# zx80_SD_12_smd_build006_3_STM32.net
KiCad netlist of a schematic drawn in EAGLE
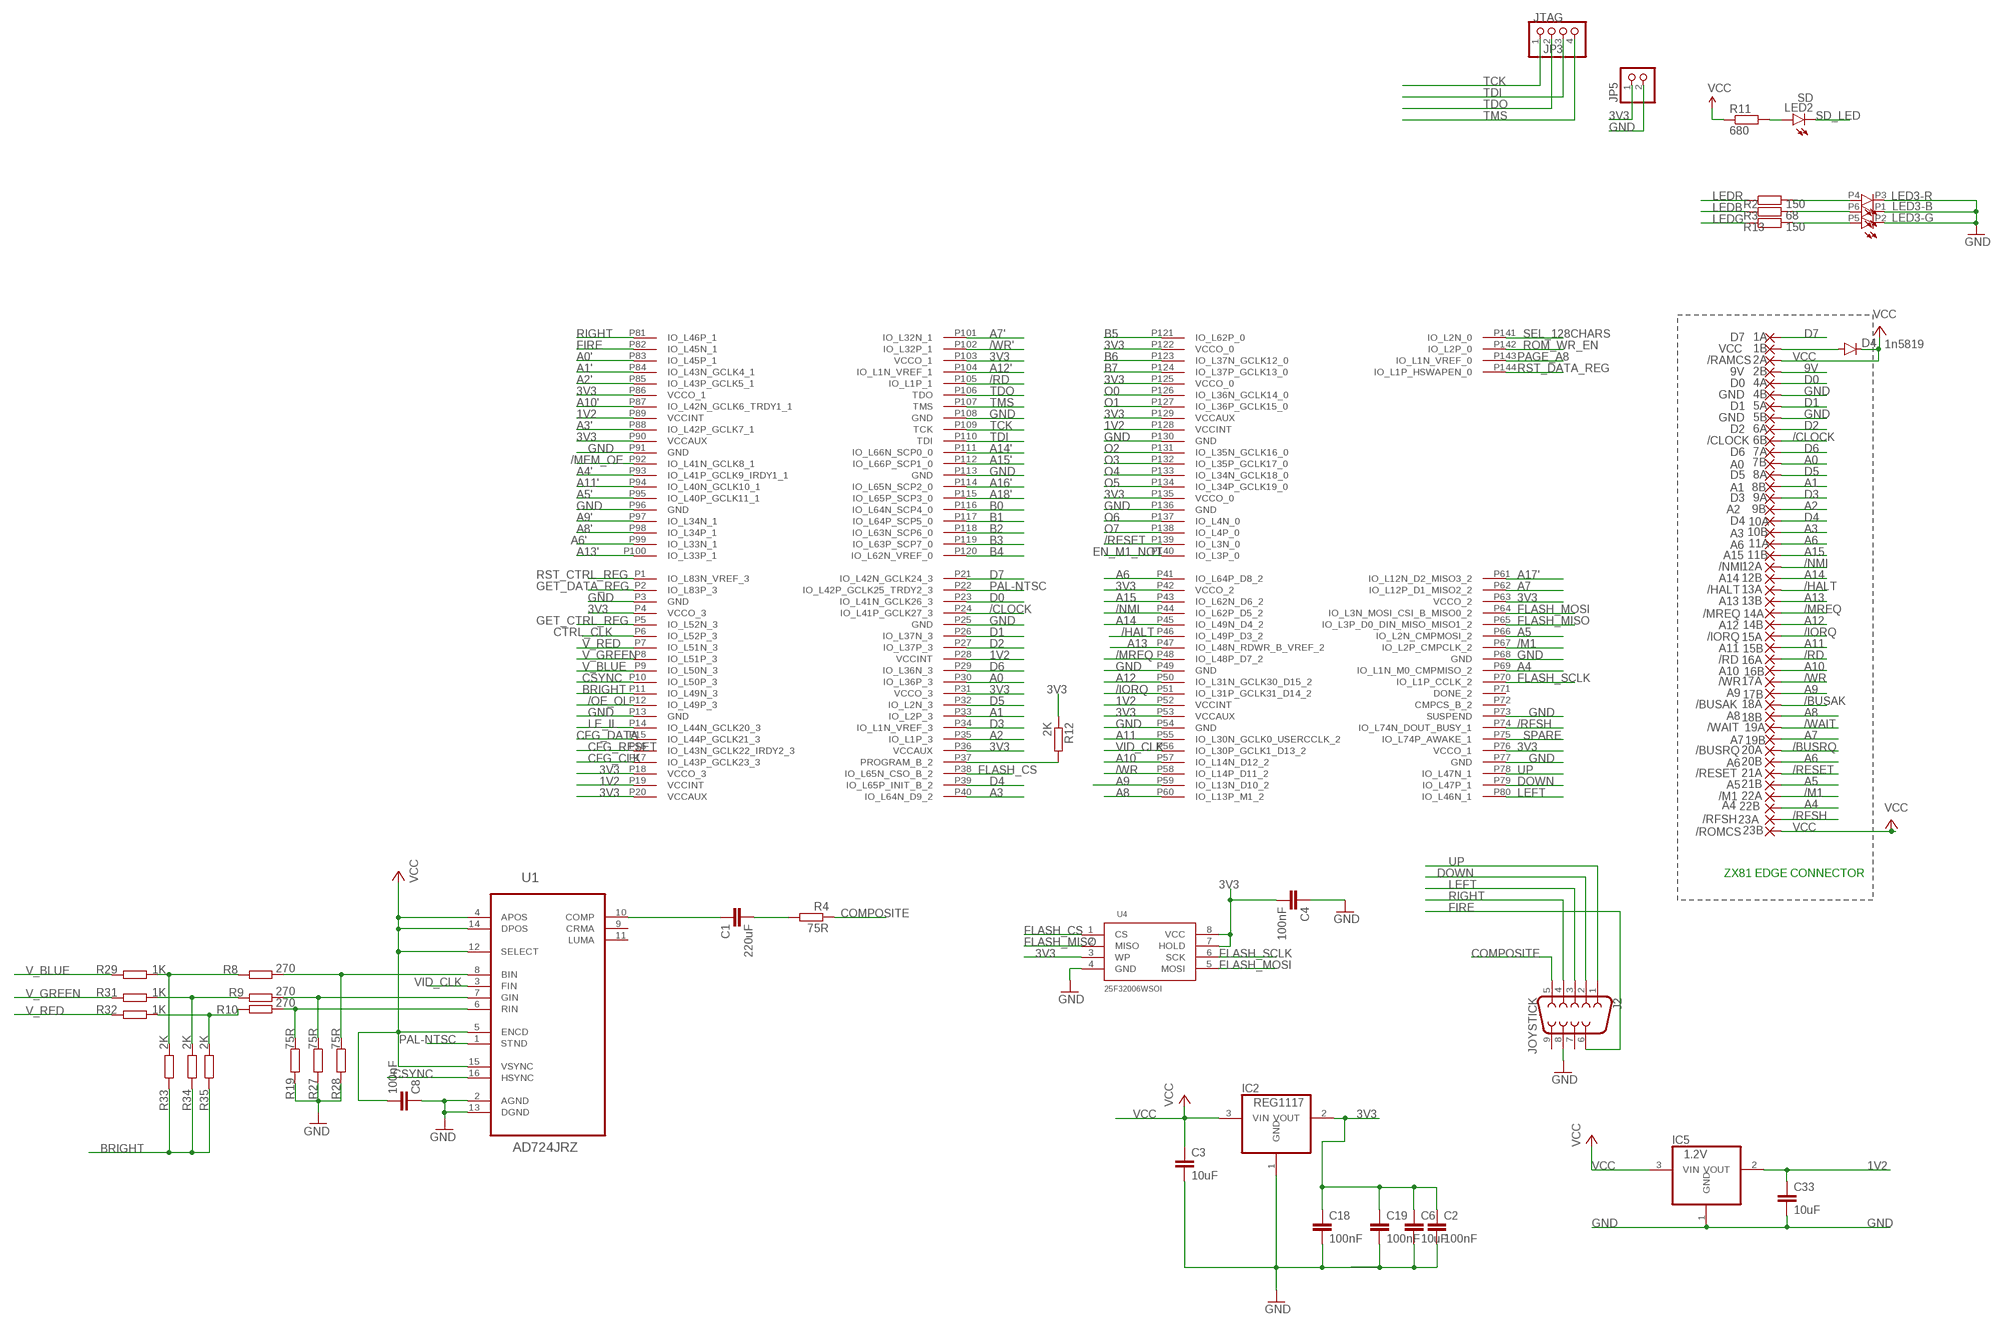
[diagram p0: schematic, sheet 1, part 1 of 2]
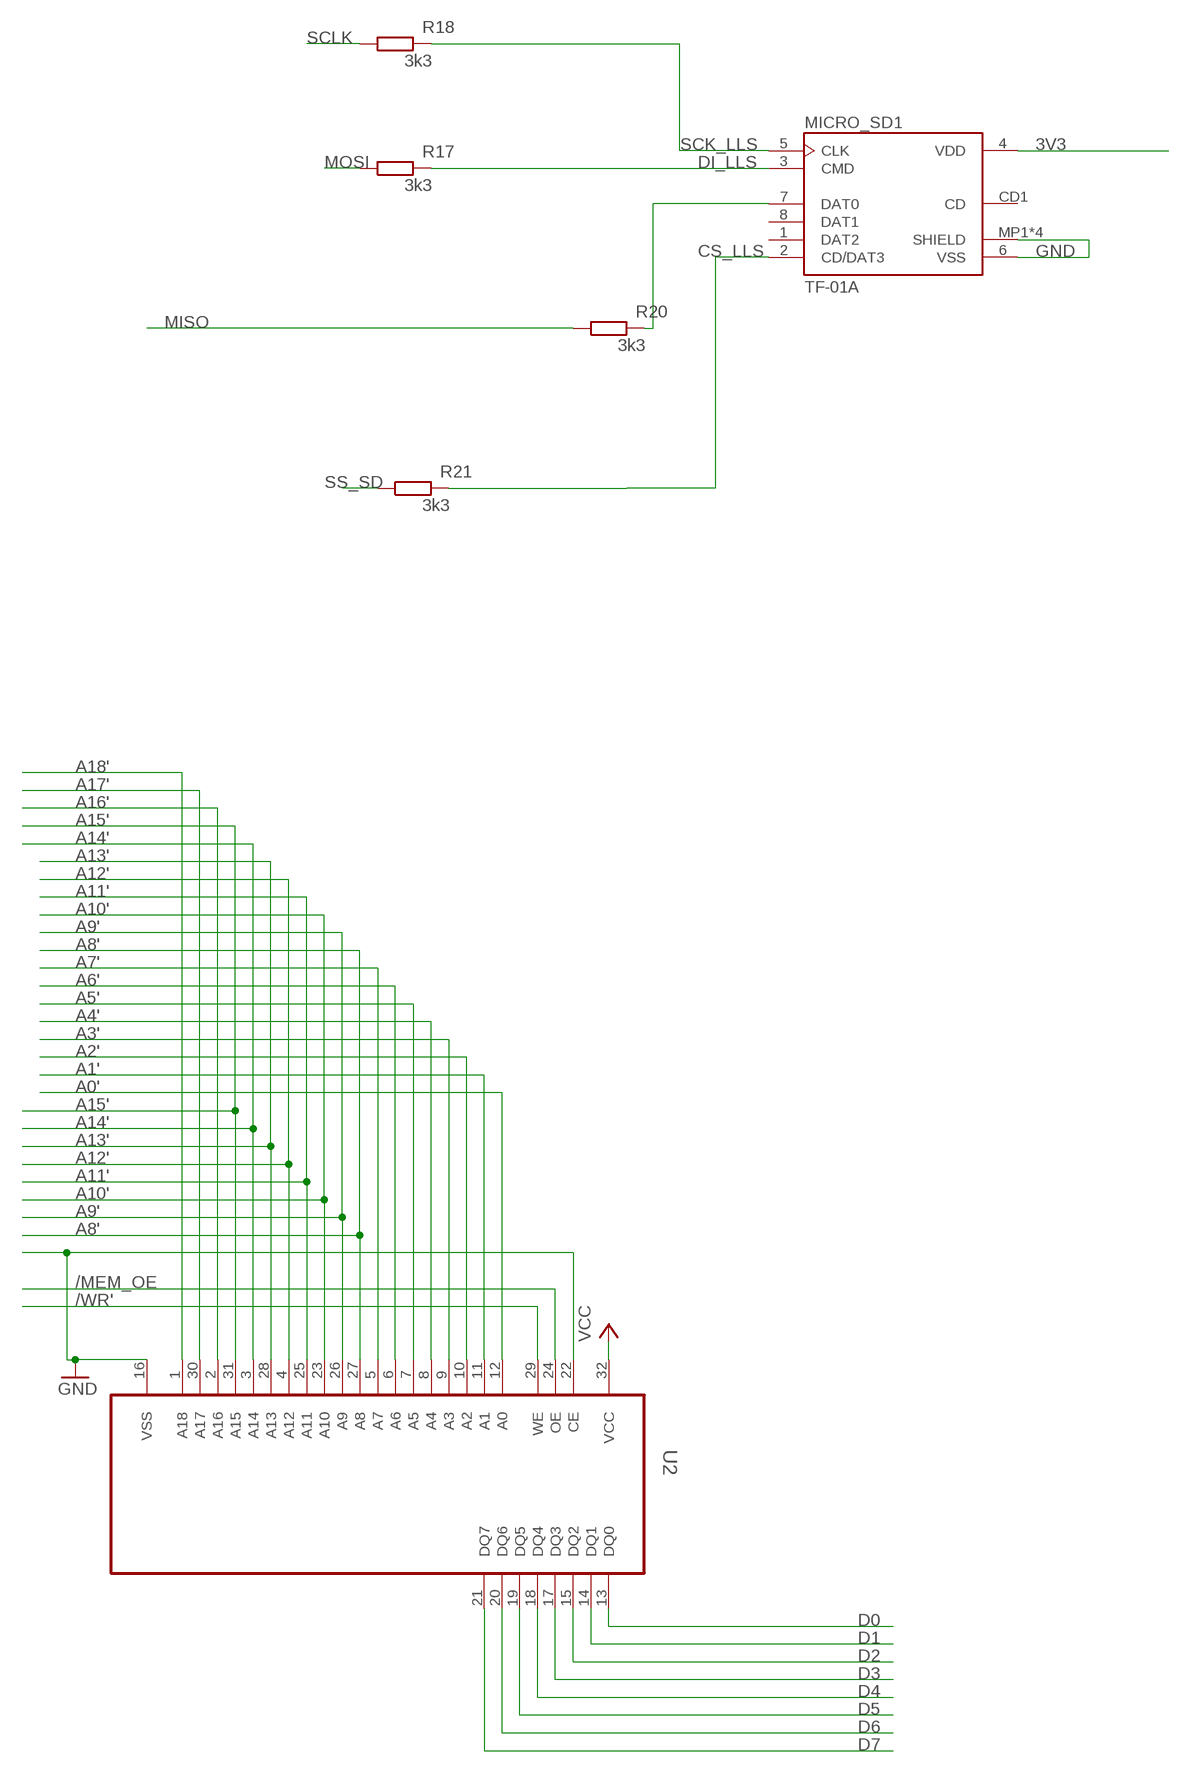
[diagram p1: schematic, sheet 1, part 2 of 2]
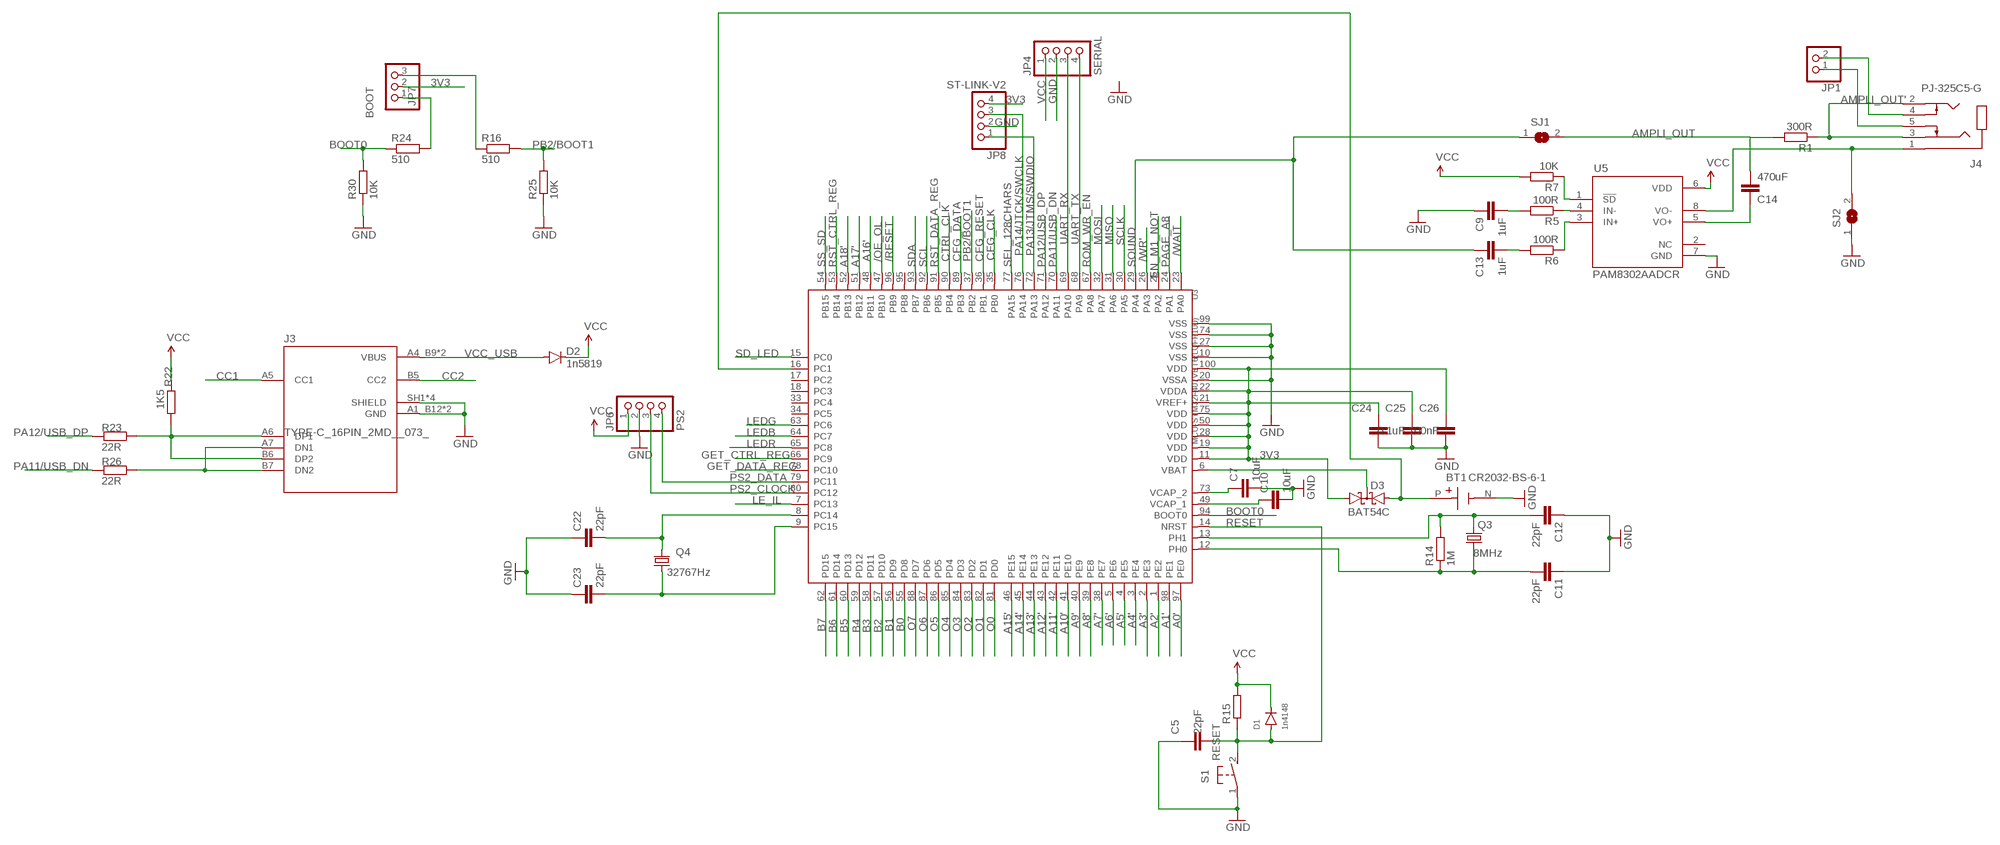
[diagram p2: schematic, sheet 2]

(export (version "E")
  (design (tool "Eeschema 10.0.6"))
  (components
    (comp (ref "BT1")
      (value "CR2032-BS-6-1")
      (footprint "eagle-import:BAT_CR2032-BS-6-1")
      (fields (field (name "MF") "Shenzhen Q&J Electronics Co. Ltd"))
      (libsource (lib "eagle-import") (part "CR2032-BS-6-1"))
    )
    (comp (ref "C5")
      (value "22pF")
      (footprint "eagle-import:C0603")
      (libsource (lib "eagle-import") (part "C-EUC0603"))
    )
    (comp (ref "C7")
      (value "10uF")
      (footprint "eagle-import:C1206")
      (libsource (lib "eagle-import") (part "C-EUC1206"))
    )
    (comp (ref "C9")
      (value "1uF")
      (footprint "eagle-import:C0603")
      (libsource (lib "eagle-import") (part "C-EUC0603"))
    )
    (comp (ref "C10")
      (value "10uF")
      (footprint "eagle-import:C1206")
      (libsource (lib "eagle-import") (part "C-EUC1206"))
    )
    (comp (ref "C11")
      (value "22pF")
      (footprint "eagle-import:C0603")
      (libsource (lib "eagle-import") (part "C-EUC0603"))
    )
    (comp (ref "C12")
      (value "22pF")
      (footprint "eagle-import:C0603")
      (libsource (lib "eagle-import") (part "C-EUC0603"))
    )
    (comp (ref "C13")
      (value "1uF")
      (footprint "eagle-import:C0603")
      (libsource (lib "eagle-import") (part "C-EUC0603"))
    )
    (comp (ref "C14")
      (value "470uF")
      (footprint "eagle-import:C0603")
      (libsource (lib "eagle-import") (part "C-EUC0603"))
    )
    (comp (ref "C22")
      (value "22pF")
      (footprint "eagle-import:C0603")
      (libsource (lib "eagle-import") (part "C-EUC0603"))
    )
    (comp (ref "C23")
      (value "22pF")
      (footprint "eagle-import:C0603")
      (libsource (lib "eagle-import") (part "C-EUC0603"))
    )
    (comp (ref "C24")
      (value "0.1uF")
      (footprint "eagle-import:C0603")
      (libsource (lib "eagle-import") (part "C-EUC0603"))
    )
    (comp (ref "C25")
      (value "0.1uF")
      (footprint "eagle-import:C0603")
      (libsource (lib "eagle-import") (part "C-EUC0603"))
    )
    (comp (ref "C26")
      (value "100nF")
      (footprint "eagle-import:C0603")
      (libsource (lib "eagle-import") (part "C-EUC0603"))
    )
    (comp (ref "D1")
      (value "1n4148")
      (footprint "eagle-import:SOD123")
      (libsource (lib "eagle-import") (part "DIODE-SOD123"))
    )
    (comp (ref "D2")
      (value "1n5819")
      (footprint "eagle-import:SOD323-W")
      (libsource (lib "eagle-import") (part "DIODE-SOD323-W"))
    )
    (comp (ref "D3")
      (value "BAT54C")
      (footprint "eagle-import:SOT23")
      (libsource (lib "eagle-import") (part "BAT54C"))
    )
    (comp (ref "J3")
      (value "TYPE-C_16PIN_2MD__073_")
      (footprint "eagle-import:SHOUHAN_TYPE-C_16PIN_2MD__073_")
      (fields (field (name "MF") "Shouhan") (field (name "MP") "TYPE-C 16PIN 2MD (073)"))
      (libsource (lib "eagle-import") (part "TYPE-C_16PIN_2MD__073_"))
    )
    (comp (ref "J4")
      (value "PJ-325C5-G")
      (footprint "eagle-import:XKB_PJ-325C5-G")
      (fields (field (name "MF") "XKB Connection"))
      (libsource (lib "eagle-import") (part "PJ-325C5-G"))
    )
    (comp (ref "JP1")
      (value "PINHD-1X2")
      (footprint "eagle-import:1X02")
      (libsource (lib "eagle-import") (part "PINHD-1X2"))
    )
    (comp (ref "JP4")
      (value "SERIAL")
      (footprint "eagle-import:1X04")
      (libsource (lib "eagle-import") (part "PINHD-1X4"))
    )
    (comp (ref "JP6")
      (value "PS2")
      (footprint "eagle-import:1X04")
      (libsource (lib "eagle-import") (part "PINHD-1X4"))
    )
    (comp (ref "JP7")
      (value "BOOT")
      (footprint "eagle-import:1X03")
      (libsource (lib "eagle-import") (part "PINHD-1X3"))
    )
    (comp (ref "JP8")
      (value "ST-LINK-V2")
      (footprint "eagle-import:1X04")
      (libsource (lib "eagle-import") (part "PINHD-1X4"))
    )
    (comp (ref "Q3")
      (value "8MHz")
      (footprint "eagle-import:3.2X2.5_KX-7")
      (libsource (lib "eagle-import") (part "KX-7"))
    )
    (comp (ref "Q4")
      (value "32767Hz")
      (footprint "eagle-import:3.2X1.5")
      (libsource (lib "eagle-import") (part "KX-327-NHT"))
    )
    (comp (ref "R1")
      (value "300R")
      (footprint "eagle-import:R0603")
      (libsource (lib "eagle-import") (part "R-EU_R0603"))
    )
    (comp (ref "R5")
      (value "100R")
      (footprint "eagle-import:R0603")
      (libsource (lib "eagle-import") (part "R-EU_R0603"))
    )
    (comp (ref "R6")
      (value "100R")
      (footprint "eagle-import:R0603")
      (libsource (lib "eagle-import") (part "R-EU_R0603"))
    )
    (comp (ref "R7")
      (value "10K")
      (footprint "eagle-import:R0603")
      (libsource (lib "eagle-import") (part "R-EU_R0603"))
    )
    (comp (ref "R14")
      (value "1M")
      (footprint "eagle-import:R0603")
      (libsource (lib "eagle-import") (part "R-EU_R0603"))
    )
    (comp (ref "R15")
      (value "3K3")
      (footprint "eagle-import:R0603")
      (libsource (lib "eagle-import") (part "R-EU_R0603"))
    )
    (comp (ref "R16")
      (value "510")
      (footprint "eagle-import:R0603")
      (libsource (lib "eagle-import") (part "R-EU_R0603"))
    )
    (comp (ref "R22")
      (value "1K5")
      (footprint "eagle-import:R0603")
      (libsource (lib "eagle-import") (part "R-EU_R0603"))
    )
    (comp (ref "R23")
      (value "22R")
      (footprint "eagle-import:R0603")
      (libsource (lib "eagle-import") (part "R-EU_R0603"))
    )
    (comp (ref "R24")
      (value "510")
      (footprint "eagle-import:R0603")
      (libsource (lib "eagle-import") (part "R-EU_R0603"))
    )
    (comp (ref "R25")
      (value "10K")
      (footprint "eagle-import:R0603")
      (libsource (lib "eagle-import") (part "R-EU_R0603"))
    )
    (comp (ref "R26")
      (value "22R")
      (footprint "eagle-import:R0603")
      (libsource (lib "eagle-import") (part "R-EU_R0603"))
    )
    (comp (ref "R30")
      (value "10K")
      (footprint "eagle-import:R0603")
      (libsource (lib "eagle-import") (part "R-EU_R0603"))
    )
    (comp (ref "S1")
      (value "RESET")
      (footprint "eagle-import:B3F-31XX")
      (fields (field (name "MPN") "B3F-3100"))
      (libsource (lib "eagle-import") (part "31-XX"))
    )
    (comp (ref "SJ1") (value "SJ") (footprint "eagle-import:SJ") (libsource (lib "eagle-import") (part "SJ")))
    (comp (ref "SJ2") (value "SJ") (footprint "eagle-import:SJ") (libsource (lib "eagle-import") (part "SJ")))
    (comp (ref "U3")
      (value "MCU-STM32F407VET6(LQFP100)")
      (footprint "eagle-import:LQFP100-0.5-13.8X13.8MM")
      (fields (field (name "MF") "STMicroelectronics") (field (name "MP") "STM32F407VET6"))
      (libsource (lib "eagle-import") (part "MCU-STM32F407VET6(LQFP100)"))
    )
    (comp (ref "U5")
      (value "PAM8302AADCR")
      (footprint "eagle-import:SOIC127P600X170-8N")
      (fields (field (name "MF") "Diodes Inc."))
      (libsource (lib "eagle-import") (part "PAM8302AADCR"))
    )
    (comp (ref "1A")
      (value "D7")
      (footprint "eagle-import:EDGEPIN")
      (libsource (lib "eagle-import") (part "SMD2EDGEPIN"))
    )
    (comp (ref "1B")
      (value "VCC")
      (footprint "eagle-import:EDGEPIN")
      (libsource (lib "eagle-import") (part "SMD2EDGEPIN"))
    )
    (comp (ref "2A")
      (value "/RAMCS")
      (footprint "eagle-import:EDGEPIN")
      (libsource (lib "eagle-import") (part "SMD2EDGEPIN"))
    )
    (comp (ref "2B")
      (value "9V")
      (footprint "eagle-import:EDGEPIN")
      (libsource (lib "eagle-import") (part "SMD2EDGEPIN"))
    )
    (comp (ref "4A")
      (value "D0")
      (footprint "eagle-import:EDGEPIN")
      (libsource (lib "eagle-import") (part "SMD2EDGEPIN"))
    )
    (comp (ref "4B")
      (value "GND")
      (footprint "eagle-import:EDGEPIN")
      (libsource (lib "eagle-import") (part "SMD2EDGEPIN"))
    )
    (comp (ref "5A")
      (value "D1")
      (footprint "eagle-import:EDGEPIN")
      (libsource (lib "eagle-import") (part "SMD2EDGEPIN"))
    )
    (comp (ref "5B")
      (value "GND")
      (footprint "eagle-import:EDGEPIN")
      (libsource (lib "eagle-import") (part "SMD2EDGEPIN"))
    )
    (comp (ref "6A")
      (value "D2")
      (footprint "eagle-import:EDGEPIN")
      (libsource (lib "eagle-import") (part "SMD2EDGEPIN"))
    )
    (comp (ref "6B")
      (value "/CLOCK")
      (footprint "eagle-import:EDGEPIN")
      (libsource (lib "eagle-import") (part "SMD2EDGEPIN"))
    )
    (comp (ref "7A")
      (value "D6")
      (footprint "eagle-import:EDGEPIN")
      (libsource (lib "eagle-import") (part "SMD2EDGEPIN"))
    )
    (comp (ref "7B")
      (value "A0")
      (footprint "eagle-import:EDGEPIN")
      (libsource (lib "eagle-import") (part "SMD2EDGEPIN"))
    )
    (comp (ref "8A")
      (value "D5")
      (footprint "eagle-import:EDGEPIN")
      (libsource (lib "eagle-import") (part "SMD2EDGEPIN"))
    )
    (comp (ref "8B")
      (value "A1")
      (footprint "eagle-import:EDGEPIN")
      (libsource (lib "eagle-import") (part "SMD2EDGEPIN"))
    )
    (comp (ref "9A")
      (value "D3")
      (footprint "eagle-import:EDGEPIN")
      (libsource (lib "eagle-import") (part "SMD2EDGEPIN"))
    )
    (comp (ref "9B")
      (value "A2")
      (footprint "eagle-import:EDGEPIN")
      (libsource (lib "eagle-import") (part "SMD2EDGEPIN"))
    )
    (comp (ref "10A")
      (value "D4")
      (footprint "eagle-import:EDGEPIN")
      (libsource (lib "eagle-import") (part "SMD2EDGEPIN"))
    )
    (comp (ref "10B")
      (value "A3")
      (footprint "eagle-import:EDGEPIN")
      (libsource (lib "eagle-import") (part "SMD2EDGEPIN"))
    )
    (comp (ref "11A")
      (value "A6")
      (footprint "eagle-import:EDGEPIN")
      (libsource (lib "eagle-import") (part "SMD2EDGEPIN"))
    )
    (comp (ref "11B")
      (value "A15")
      (footprint "eagle-import:EDGEPIN")
      (libsource (lib "eagle-import") (part "SMD2EDGEPIN"))
    )
    (comp (ref "12A")
      (value "/NMI")
      (footprint "eagle-import:EDGEPIN")
      (libsource (lib "eagle-import") (part "SMD2EDGEPIN"))
    )
    (comp (ref "12B")
      (value "A14")
      (footprint "eagle-import:EDGEPIN")
      (libsource (lib "eagle-import") (part "SMD2EDGEPIN"))
    )
    (comp (ref "13A")
      (value "/HALT")
      (footprint "eagle-import:EDGEPIN")
      (libsource (lib "eagle-import") (part "SMD2EDGEPIN"))
    )
    (comp (ref "13B")
      (value "A13")
      (footprint "eagle-import:EDGEPIN")
      (libsource (lib "eagle-import") (part "SMD2EDGEPIN"))
    )
    (comp (ref "14A")
      (value "/MREQ")
      (footprint "eagle-import:EDGEPIN")
      (libsource (lib "eagle-import") (part "SMD2EDGEPIN"))
    )
    (comp (ref "14B")
      (value "A12")
      (footprint "eagle-import:EDGEPIN")
      (libsource (lib "eagle-import") (part "SMD2EDGEPIN"))
    )
    (comp (ref "15A")
      (value "/IORQ")
      (footprint "eagle-import:EDGEPIN")
      (libsource (lib "eagle-import") (part "SMD2EDGEPIN"))
    )
    (comp (ref "15B")
      (value "A11")
      (footprint "eagle-import:EDGEPIN")
      (libsource (lib "eagle-import") (part "SMD2EDGEPIN"))
    )
    (comp (ref "16A")
      (value "/RD")
      (footprint "eagle-import:EDGEPIN")
      (libsource (lib "eagle-import") (part "SMD2EDGEPIN"))
    )
    (comp (ref "16B")
      (value "A10")
      (footprint "eagle-import:EDGEPIN")
      (libsource (lib "eagle-import") (part "SMD2EDGEPIN"))
    )
    (comp (ref "17A")
      (value "/WR")
      (footprint "eagle-import:EDGEPIN")
      (libsource (lib "eagle-import") (part "SMD2EDGEPIN"))
    )
    (comp (ref "17B")
      (value "A9")
      (footprint "eagle-import:EDGEPIN")
      (libsource (lib "eagle-import") (part "SMD2EDGEPIN"))
    )
    (comp (ref "18A")
      (value "/BUSAK")
      (footprint "eagle-import:EDGEPIN")
      (libsource (lib "eagle-import") (part "SMD2EDGEPIN"))
    )
    (comp (ref "18B")
      (value "A8")
      (footprint "eagle-import:EDGEPIN")
      (libsource (lib "eagle-import") (part "SMD2EDGEPIN"))
    )
    (comp (ref "19A")
      (value "/WAIT")
      (footprint "eagle-import:EDGEPIN")
      (libsource (lib "eagle-import") (part "SMD2EDGEPIN"))
    )
    (comp (ref "19B")
      (value "A7")
      (footprint "eagle-import:EDGEPIN")
      (libsource (lib "eagle-import") (part "SMD2EDGEPIN"))
    )
    (comp (ref "20A")
      (value "/BUSRQ")
      (footprint "eagle-import:EDGEPIN")
      (libsource (lib "eagle-import") (part "SMD2EDGEPIN"))
    )
    (comp (ref "20B")
      (value "A6")
      (footprint "eagle-import:EDGEPIN")
      (libsource (lib "eagle-import") (part "SMD2EDGEPIN"))
    )
    (comp (ref "21A")
      (value "/RESET")
      (footprint "eagle-import:EDGEPIN")
      (libsource (lib "eagle-import") (part "SMD2EDGEPIN"))
    )
    (comp (ref "21B")
      (value "A5")
      (footprint "eagle-import:EDGEPIN")
      (libsource (lib "eagle-import") (part "SMD2EDGEPIN"))
    )
    (comp (ref "22A")
      (value "/M1")
      (footprint "eagle-import:EDGEPIN")
      (libsource (lib "eagle-import") (part "SMD2EDGEPIN"))
    )
    (comp (ref "22B")
      (value "A4")
      (footprint "eagle-import:EDGEPIN")
      (libsource (lib "eagle-import") (part "SMD2EDGEPIN"))
    )
    (comp (ref "23A")
      (value "/RFSH")
      (footprint "eagle-import:EDGEPIN")
      (libsource (lib "eagle-import") (part "SMD2EDGEPIN"))
    )
    (comp (ref "23B")
      (value "/ROMCS")
      (footprint "eagle-import:EDGEPIN")
      (libsource (lib "eagle-import") (part "SMD2EDGEPIN"))
    )
    (comp (ref "C1")
      (value "220uF")
      (footprint "eagle-import:C0603K")
      (libsource (lib "eagle-import") (part "C-EUC0603K"))
    )
    (comp (ref "C2")
      (value "100nF")
      (footprint "eagle-import:C0603")
      (libsource (lib "eagle-import") (part "C-EUC0603"))
    )
    (comp (ref "C3")
      (value "10uF")
      (footprint "eagle-import:C0603")
      (libsource (lib "eagle-import") (part "C-EUC0603"))
    )
    (comp (ref "C4")
      (value "100nF")
      (footprint "eagle-import:C0603")
      (libsource (lib "eagle-import") (part "C-EUC0603"))
    )
    (comp (ref "C6")
      (value "10uF")
      (footprint "eagle-import:C0603")
      (libsource (lib "eagle-import") (part "C-EUC0603"))
    )
    (comp (ref "C8")
      (value "100nF")
      (footprint "eagle-import:C0603K")
      (libsource (lib "eagle-import") (part "C-EUC0603K"))
    )
    (comp (ref "C18")
      (value "100nF")
      (footprint "eagle-import:C0603")
      (libsource (lib "eagle-import") (part "C-EUC0603"))
    )
    (comp (ref "C19")
      (value "100nF")
      (footprint "eagle-import:C0603")
      (libsource (lib "eagle-import") (part "C-EUC0603"))
    )
    (comp (ref "C33")
      (value "10uF")
      (footprint "eagle-import:C0603")
      (libsource (lib "eagle-import") (part "C-EUC0603"))
    )
    (comp (ref "D4")
      (value "1n5819")
      (footprint "eagle-import:SOD323-W")
      (libsource (lib "eagle-import") (part "DIODE-SOD323-W"))
    )
    (comp (ref "IC2")
      (value "REG1117")
      (footprint "eagle-import:SOT223")
      (libsource (lib "eagle-import") (part "REG1117"))
    )
    (comp (ref "IC5")
      (value "1.2V")
      (footprint "eagle-import:SOT223")
      (fields (field (name "MPN") "REG1117"))
      (libsource (lib "eagle-import") (part "REG1117"))
    )
    (comp (ref "J2")
      (value "JOYSTICK")
      (footprint "eagle-import:DB9_MALE")
      (libsource (lib "eagle-import") (part "DB9MALE"))
    )
    (comp (ref "JP3")
      (value "JTAG")
      (footprint "eagle-import:1X04")
      (libsource (lib "eagle-import") (part "PINHD-1X4"))
    )
    (comp (ref "JP5")
      (value "PINHD-1X2")
      (footprint "eagle-import:1X02")
      (libsource (lib "eagle-import") (part "PINHD-1X2"))
    )
    (comp (ref "LED2")
      (value "SD")
      (footprint "eagle-import:CHIPLED_0805")
      (libsource (lib "eagle-import") (part "LEDCHIPLED_0805"))
    )
    (comp (ref "LED3")
      (value "STATUS")
      (footprint "eagle-import:3535-PLCC6")
      (libsource (lib "eagle-import") (part "3535RGB3535RGB"))
    )
    (comp (ref "MICRO_SD1")
      (value "TF-01A")
      (footprint "eagle-import:TF-01A")
      (fields (field (name "MF") "HRO Electronics Co., Ltd."))
      (libsource (lib "eagle-import") (part "TF-01A"))
    )
    (comp (ref "R2")
      (value "150")
      (footprint "eagle-import:R0603")
      (libsource (lib "eagle-import") (part "R-EU_R0603"))
    )
    (comp (ref "R3")
      (value "68")
      (footprint "eagle-import:R0603")
      (libsource (lib "eagle-import") (part "R-EU_R0603"))
    )
    (comp (ref "R4")
      (value "75R")
      (footprint "eagle-import:R0603")
      (libsource (lib "eagle-import") (part "R-EU_R0603"))
    )
    (comp (ref "R8")
      (value "270")
      (footprint "eagle-import:R0402")
      (libsource (lib "eagle-import") (part "R-EU_R0402"))
    )
    (comp (ref "R9")
      (value "270")
      (footprint "eagle-import:R0402")
      (libsource (lib "eagle-import") (part "R-EU_R0402"))
    )
    (comp (ref "R10")
      (value "270")
      (footprint "eagle-import:R0402")
      (libsource (lib "eagle-import") (part "R-EU_R0402"))
    )
    (comp (ref "R11")
      (value "680")
      (footprint "eagle-import:R0603")
      (libsource (lib "eagle-import") (part "R-EU_R0603"))
    )
    (comp (ref "R12")
      (value "2K")
      (footprint "eagle-import:R0603")
      (libsource (lib "eagle-import") (part "R-EU_R0603"))
    )
    (comp (ref "R13")
      (value "150")
      (footprint "eagle-import:R0603")
      (libsource (lib "eagle-import") (part "R-EU_R0603"))
    )
    (comp (ref "R17")
      (value "3k3")
      (footprint "eagle-import:R0603")
      (libsource (lib "eagle-import") (part "R-EU_R0603"))
    )
    (comp (ref "R18")
      (value "3k3")
      (footprint "eagle-import:R0603")
      (libsource (lib "eagle-import") (part "R-EU_R0603"))
    )
    (comp (ref "R19")
      (value "75R")
      (footprint "eagle-import:R0402")
      (libsource (lib "eagle-import") (part "R-EU_R0402"))
    )
    (comp (ref "R20")
      (value "3k3")
      (footprint "eagle-import:R0603")
      (libsource (lib "eagle-import") (part "R-EU_R0603"))
    )
    (comp (ref "R21")
      (value "3k3")
      (footprint "eagle-import:R0603")
      (libsource (lib "eagle-import") (part "R-EU_R0603"))
    )
    (comp (ref "R27")
      (value "75R")
      (footprint "eagle-import:R0402")
      (libsource (lib "eagle-import") (part "R-EU_R0402"))
    )
    (comp (ref "R28")
      (value "75R")
      (footprint "eagle-import:R0402")
      (libsource (lib "eagle-import") (part "R-EU_R0402"))
    )
    (comp (ref "R29")
      (value "1K")
      (footprint "eagle-import:R0402")
      (libsource (lib "eagle-import") (part "R-EU_R0402"))
    )
    (comp (ref "R31")
      (value "1K")
      (footprint "eagle-import:R0402")
      (libsource (lib "eagle-import") (part "R-EU_R0402"))
    )
    (comp (ref "R32")
      (value "1K")
      (footprint "eagle-import:R0402")
      (libsource (lib "eagle-import") (part "R-EU_R0402"))
    )
    (comp (ref "R33")
      (value "2K")
      (footprint "eagle-import:R0402")
      (libsource (lib "eagle-import") (part "R-EU_R0402"))
    )
    (comp (ref "R34")
      (value "2K")
      (footprint "eagle-import:R0402")
      (libsource (lib "eagle-import") (part "R-EU_R0402"))
    )
    (comp (ref "R35")
      (value "2K")
      (footprint "eagle-import:R0402")
      (libsource (lib "eagle-import") (part "R-EU_R0402"))
    )
    (comp (ref "U$1")
      (value "XC6SLX9-2TQG144C")
      (footprint "eagle-import:TQ144")
      (fields (field (name "MF") "Xilinx Inc."))
      (libsource (lib "eagle-import") (part "XC6SLX9-2TQG144C"))
    )
    (comp (ref "U1")
      (value "AD724JRZ")
      (footprint "eagle-import:SOIC127P1032X265-16N")
      (fields (field (name "MF") "Analog Devices") (field (name "MP") "AD724JR"))
      (libsource (lib "eagle-import") (part "AD724JRZ"))
    )
    (comp (ref "U2")
      (value "AS6C4008")
      (footprint "eagle-import:SOP32-5")
      (libsource (lib "eagle-import") (part "AS6C4008-55SINSOP5"))
    )
    (comp (ref "U4")
      (value "25F32006WSOI")
      (footprint "eagle-import:SO08-EIAJ")
      (libsource (lib "eagle-import") (part "SPI_FLASH-X25XXSMD1"))
    )
  )
  (nets
    (net (code "1") (name "1V2") (class "Default")
      (node (ref "C33") (pin "1") (pinfunction "1_1") (pintype "passive"))
      (node (ref "IC5") (pin "2") (pinfunction "VOUT_2") (pintype "output"))
      (node (ref "U$1") (pin "P128") (pinfunction "VCCINT_P128") (pintype "bidirectional"))
      (node (ref "U$1") (pin "P19") (pinfunction "VCCINT_P19") (pintype "bidirectional"))
      (node (ref "U$1") (pin "P28") (pinfunction "VCCINT_P28") (pintype "bidirectional"))
      (node (ref "U$1") (pin "P52") (pinfunction "VCCINT_P52") (pintype "bidirectional"))
      (node (ref "U$1") (pin "P89") (pinfunction "VCCINT_P89") (pintype "bidirectional"))
    )
    (net (code "2") (name "3V3") (class "Default")
      (node (ref "C18") (pin "1") (pinfunction "1_1") (pintype "passive"))
      (node (ref "C19") (pin "1") (pinfunction "1_1") (pintype "passive"))
      (node (ref "C2") (pin "1") (pinfunction "1_1") (pintype "passive"))
      (node (ref "C24") (pin "1") (pinfunction "1_1") (pintype "passive"))
      (node (ref "C25") (pin "1") (pinfunction "1_1") (pintype "passive"))
      (node (ref "C26") (pin "1") (pinfunction "1_1") (pintype "passive"))
      (node (ref "C4") (pin "2") (pinfunction "2_2") (pintype "passive"))
      (node (ref "C6") (pin "1") (pinfunction "1_1") (pintype "passive"))
      (node (ref "D3") (pin "1") (pinfunction "A1_1") (pintype "passive"))
      (node (ref "IC2") (pin "2") (pinfunction "VOUT_2") (pintype "output"))
      (node (ref "JP5") (pin "1") (pinfunction "1_1") (pintype "passive"))
      (node (ref "JP7") (pin "2") (pinfunction "2_2") (pintype "passive"))
      (node (ref "JP8") (pin "4") (pinfunction "4_4") (pintype "passive"))
      (node (ref "MICRO_SD1") (pin "4") (pinfunction "VDD_4") (pintype "power_in"))
      (node (ref "R12") (pin "1") (pinfunction "1_1") (pintype "passive"))
      (node (ref "U$1") (pin "P103") (pinfunction "VCCO_1_P103") (pintype "bidirectional"))
      (node (ref "U$1") (pin "P122") (pinfunction "VCCO_0_P122") (pintype "bidirectional"))
      (node (ref "U$1") (pin "P125") (pinfunction "VCCO_0_P125") (pintype "bidirectional"))
      (node (ref "U$1") (pin "P129") (pinfunction "VCCAUX_P129") (pintype "bidirectional"))
      (node (ref "U$1") (pin "P135") (pinfunction "VCCO_0_P135") (pintype "bidirectional"))
      (node (ref "U$1") (pin "P18") (pinfunction "VCCO_3_P18") (pintype "bidirectional"))
      (node (ref "U$1") (pin "P20") (pinfunction "VCCAUX_P20") (pintype "bidirectional"))
      (node (ref "U$1") (pin "P31") (pinfunction "VCCO_3_P31") (pintype "bidirectional"))
      (node (ref "U$1") (pin "P36") (pinfunction "VCCAUX_P36") (pintype "bidirectional"))
      (node (ref "U$1") (pin "P4") (pinfunction "VCCO_3_P4") (pintype "bidirectional"))
      (node (ref "U$1") (pin "P42") (pinfunction "VCCO_2_P42") (pintype "bidirectional"))
      (node (ref "U$1") (pin "P53") (pinfunction "VCCAUX_P53") (pintype "bidirectional"))
      (node (ref "U$1") (pin "P63") (pinfunction "VCCO_2_P63") (pintype "bidirectional"))
      (node (ref "U$1") (pin "P76") (pinfunction "VCCO_1_P76") (pintype "bidirectional"))
      (node (ref "U$1") (pin "P86") (pinfunction "VCCO_1_P86") (pintype "bidirectional"))
      (node (ref "U$1") (pin "P90") (pinfunction "VCCAUX_P90") (pintype "bidirectional"))
      (node (ref "U3") (pin "100") (pinfunction "VDD_100") (pintype "bidirectional"))
      (node (ref "U3") (pin "11") (pinfunction "VDD_11") (pintype "bidirectional"))
      (node (ref "U3") (pin "19") (pinfunction "VDD_19") (pintype "bidirectional"))
      (node (ref "U3") (pin "21") (pinfunction "VREF+_21") (pintype "bidirectional"))
      (node (ref "U3") (pin "22") (pinfunction "VDDA_22") (pintype "bidirectional"))
      (node (ref "U3") (pin "28") (pinfunction "VDD_28") (pintype "bidirectional"))
      (node (ref "U3") (pin "50") (pinfunction "VDD_50") (pintype "bidirectional"))
      (node (ref "U3") (pin "75") (pinfunction "VDD_75") (pintype "bidirectional"))
      (node (ref "U4") (pin "3") (pinfunction "WP_3") (pintype "bidirectional"))
      (node (ref "U4") (pin "7") (pinfunction "HOLD_7") (pintype "bidirectional"))
      (node (ref "U4") (pin "8") (pinfunction "VCC_8") (pintype "power_in"))
    )
    (net (code "3") (name "9V") (class "Default")
      (node (ref "2B") (pin "1") (pinfunction "P_1") (pintype "passive"))
    )
    (net (code "4") (name "A0") (class "Default")
      (node (ref "7B") (pin "1") (pinfunction "P_1") (pintype "passive"))
      (node (ref "U$1") (pin "P30") (pinfunction "IO_L36P_3_P30") (pintype "bidirectional"))
    )
    (net (code "5") (name "A0'") (class "Default")
      (node (ref "U$1") (pin "P83") (pinfunction "IO_L45P_1_P83") (pintype "bidirectional"))
      (node (ref "U2") (pin "12") (pinfunction "A0_12") (pintype "input"))
      (node (ref "U3") (pin "97") (pinfunction "PE0_97") (pintype "bidirectional"))
    )
    (net (code "6") (name "A1") (class "Default")
      (node (ref "8B") (pin "1") (pinfunction "P_1") (pintype "passive"))
      (node (ref "U$1") (pin "P33") (pinfunction "IO_L2P_3_P33") (pintype "bidirectional"))
    )
    (net (code "7") (name "A1'") (class "Default")
      (node (ref "U$1") (pin "P84") (pinfunction "IO_L43N_GCLK4_1_P84") (pintype "bidirectional"))
      (node (ref "U2") (pin "11") (pinfunction "A1_11") (pintype "input"))
      (node (ref "U3") (pin "98") (pinfunction "PE1_98") (pintype "bidirectional"))
    )
    (net (code "8") (name "A2") (class "Default")
      (node (ref "9B") (pin "1") (pinfunction "P_1") (pintype "passive"))
      (node (ref "U$1") (pin "P35") (pinfunction "IO_L1P_3_P35") (pintype "bidirectional"))
    )
    (net (code "9") (name "A2'") (class "Default")
      (node (ref "U$1") (pin "P85") (pinfunction "IO_L43P_GCLK5_1_P85") (pintype "bidirectional"))
      (node (ref "U2") (pin "10") (pinfunction "A2_10") (pintype "input"))
      (node (ref "U3") (pin "1") (pinfunction "PE2_1") (pintype "bidirectional"))
    )
    (net (code "10") (name "A3") (class "Default")
      (node (ref "10B") (pin "1") (pinfunction "P_1") (pintype "passive"))
      (node (ref "U$1") (pin "P40") (pinfunction "IO_L64N_D9_2_P40") (pintype "bidirectional"))
    )
    (net (code "11") (name "A3'") (class "Default")
      (node (ref "U$1") (pin "P88") (pinfunction "IO_L42P_GCLK7_1_P88") (pintype "bidirectional"))
      (node (ref "U2") (pin "9") (pinfunction "A3_9") (pintype "input"))
      (node (ref "U3") (pin "2") (pinfunction "PE3_2") (pintype "bidirectional"))
    )
    (net (code "12") (name "A4") (class "Default")
      (node (ref "22B") (pin "1") (pinfunction "P_1") (pintype "passive"))
      (node (ref "U$1") (pin "P69") (pinfunction "IO_L1N_M0_CMPMISO_2_P69") (pintype "bidirectional"))
    )
    (net (code "13") (name "A4'") (class "Default")
      (node (ref "U$1") (pin "P93") (pinfunction "IO_L41P_GCLK9_IRDY1_1_P93") (pintype "bidirectional"))
      (node (ref "U2") (pin "8") (pinfunction "A4_8") (pintype "input"))
      (node (ref "U3") (pin "3") (pinfunction "PE4_3") (pintype "bidirectional"))
    )
    (net (code "14") (name "A5") (class "Default")
      (node (ref "21B") (pin "1") (pinfunction "P_1") (pintype "passive"))
      (node (ref "U$1") (pin "P66") (pinfunction "IO_L2N_CMPMOSI_2_P66") (pintype "bidirectional"))
    )
    (net (code "15") (name "A5'") (class "Default")
      (node (ref "U$1") (pin "P95") (pinfunction "IO_L40P_GCLK11_1_P95") (pintype "bidirectional"))
      (node (ref "U2") (pin "7") (pinfunction "A5_7") (pintype "input"))
      (node (ref "U3") (pin "4") (pinfunction "PE5_4") (pintype "bidirectional"))
    )
    (net (code "16") (name "A6") (class "Default")
      (node (ref "11A") (pin "1") (pinfunction "P_1") (pintype "passive"))
      (node (ref "20B") (pin "1") (pinfunction "P_1") (pintype "passive"))
      (node (ref "U$1") (pin "P41") (pinfunction "IO_L64P_D8_2_P41") (pintype "bidirectional"))
    )
    (net (code "17") (name "A6'") (class "Default")
      (node (ref "U$1") (pin "P99") (pinfunction "IO_L33N_1_P99") (pintype "bidirectional"))
      (node (ref "U2") (pin "6") (pinfunction "A6_6") (pintype "input"))
      (node (ref "U3") (pin "5") (pinfunction "PE6_5") (pintype "bidirectional"))
    )
    (net (code "18") (name "A7") (class "Default")
      (node (ref "19B") (pin "1") (pinfunction "P_1") (pintype "passive"))
      (node (ref "U$1") (pin "P62") (pinfunction "IO_L12P_D1_MISO2_2_P62") (pintype "bidirectional"))
    )
    (net (code "19") (name "A7'") (class "Default")
      (node (ref "U$1") (pin "P101") (pinfunction "IO_L32N_1_P101") (pintype "bidirectional"))
      (node (ref "U2") (pin "5") (pinfunction "A7_5") (pintype "input"))
      (node (ref "U3") (pin "38") (pinfunction "PE7_38") (pintype "bidirectional"))
    )
    (net (code "20") (name "A8") (class "Default")
      (node (ref "18B") (pin "1") (pinfunction "P_1") (pintype "passive"))
      (node (ref "U$1") (pin "P60") (pinfunction "IO_L13P_M1_2_P60") (pintype "bidirectional"))
    )
    (net (code "21") (name "A8'") (class "Default")
      (node (ref "U$1") (pin "P98") (pinfunction "IO_L34P_1_P98") (pintype "bidirectional"))
      (node (ref "U2") (pin "27") (pinfunction "A8_27") (pintype "input"))
      (node (ref "U3") (pin "39") (pinfunction "PE8_39") (pintype "bidirectional"))
    )
    (net (code "22") (name "A9") (class "Default")
      (node (ref "17B") (pin "1") (pinfunction "P_1") (pintype "passive"))
      (node (ref "U$1") (pin "P59") (pinfunction "IO_L13N_D10_2_P59") (pintype "bidirectional"))
    )
    (net (code "23") (name "A9'") (class "Default")
      (node (ref "U$1") (pin "P97") (pinfunction "IO_L34N_1_P97") (pintype "bidirectional"))
      (node (ref "U2") (pin "26") (pinfunction "A9_26") (pintype "input"))
      (node (ref "U3") (pin "40") (pinfunction "PE9_40") (pintype "bidirectional"))
    )
    (net (code "24") (name "A10") (class "Default")
      (node (ref "16B") (pin "1") (pinfunction "P_1") (pintype "passive"))
      (node (ref "U$1") (pin "P57") (pinfunction "IO_L14N_D12_2_P57") (pintype "bidirectional"))
    )
    (net (code "25") (name "A10'") (class "Default")
      (node (ref "U$1") (pin "P87") (pinfunction "IO_L42N_GCLK6_TRDY1_1_P87") (pintype "bidirectional"))
      (node (ref "U2") (pin "23") (pinfunction "A10_23") (pintype "input"))
      (node (ref "U3") (pin "41") (pinfunction "PE10_41") (pintype "bidirectional"))
    )
    (net (code "26") (name "A11") (class "Default")
      (node (ref "15B") (pin "1") (pinfunction "P_1") (pintype "passive"))
      (node (ref "U$1") (pin "P55") (pinfunction "IO_L30N_GCLK0_USERCCLK_2_P55") (pintype "bidirectional"))
    )
    (net (code "27") (name "A11'") (class "Default")
      (node (ref "U$1") (pin "P94") (pinfunction "IO_L40N_GCLK10_1_P94") (pintype "bidirectional"))
      (node (ref "U2") (pin "25") (pinfunction "A11_25") (pintype "input"))
      (node (ref "U3") (pin "42") (pinfunction "PE11_42") (pintype "bidirectional"))
    )
    (net (code "28") (name "A12") (class "Default")
      (node (ref "14B") (pin "1") (pinfunction "P_1") (pintype "passive"))
      (node (ref "U$1") (pin "P50") (pinfunction "IO_L31N_GCLK30_D15_2_P50") (pintype "bidirectional"))
    )
    (net (code "29") (name "A12'") (class "Default")
      (node (ref "U$1") (pin "P104") (pinfunction "IO_L1N_VREF_1_P104") (pintype "bidirectional"))
      (node (ref "U2") (pin "4") (pinfunction "A12_4") (pintype "input"))
      (node (ref "U3") (pin "43") (pinfunction "PE12_43") (pintype "bidirectional"))
    )
    (net (code "30") (name "A13") (class "Default")
      (node (ref "13B") (pin "1") (pinfunction "P_1") (pintype "passive"))
      (node (ref "U$1") (pin "P47") (pinfunction "IO_L48N_RDWR_B_VREF_2_P47") (pintype "bidirectional"))
    )
    (net (code "31") (name "A13'") (class "Default")
      (node (ref "U$1") (pin "P100") (pinfunction "IO_L33P_1_P100") (pintype "bidirectional"))
      (node (ref "U2") (pin "28") (pinfunction "A13_28") (pintype "input"))
      (node (ref "U3") (pin "44") (pinfunction "PE13_44") (pintype "bidirectional"))
    )
    (net (code "32") (name "A14") (class "Default")
      (node (ref "12B") (pin "1") (pinfunction "P_1") (pintype "passive"))
      (node (ref "U$1") (pin "P45") (pinfunction "IO_L49N_D4_2_P45") (pintype "bidirectional"))
    )
    (net (code "33") (name "A14'") (class "Default")
      (node (ref "U$1") (pin "P111") (pinfunction "IO_L66N_SCP0_0_P111") (pintype "bidirectional"))
      (node (ref "U2") (pin "3") (pinfunction "A14_3") (pintype "input"))
      (node (ref "U3") (pin "45") (pinfunction "PE14_45") (pintype "bidirectional"))
    )
    (net (code "34") (name "A15") (class "Default")
      (node (ref "11B") (pin "1") (pinfunction "P_1") (pintype "passive"))
      (node (ref "U$1") (pin "P43") (pinfunction "IO_L62N_D6_2_P43") (pintype "bidirectional"))
    )
    (net (code "35") (name "A15'") (class "Default")
      (node (ref "U$1") (pin "P112") (pinfunction "IO_L66P_SCP1_0_P112") (pintype "bidirectional"))
      (node (ref "U2") (pin "31") (pinfunction "A15_31") (pintype "input"))
      (node (ref "U3") (pin "46") (pinfunction "PE15_46") (pintype "bidirectional"))
    )
    (net (code "36") (name "A16'") (class "Default")
      (node (ref "U$1") (pin "P114") (pinfunction "IO_L65N_SCP2_0_P114") (pintype "bidirectional"))
      (node (ref "U2") (pin "2") (pinfunction "A16_2") (pintype "input"))
      (node (ref "U3") (pin "48") (pinfunction "PB11_48") (pintype "bidirectional"))
    )
    (net (code "37") (name "A17'") (class "Default")
      (node (ref "U$1") (pin "P61") (pinfunction "IO_L12N_D2_MISO3_2_P61") (pintype "bidirectional"))
      (node (ref "U2") (pin "30") (pinfunction "A17_30") (pintype "input"))
      (node (ref "U3") (pin "51") (pinfunction "PB12_51") (pintype "bidirectional"))
    )
    (net (code "38") (name "A18'") (class "Default")
      (node (ref "U$1") (pin "P115") (pinfunction "IO_L65P_SCP3_0_P115") (pintype "bidirectional"))
      (node (ref "U2") (pin "1") (pinfunction "A18_1") (pintype "input"))
      (node (ref "U3") (pin "52") (pinfunction "PB13_52") (pintype "bidirectional"))
    )
    (net (code "39") (name "AMPLI_OUT") (class "Default")
      (node (ref "C14") (pin "2") (pinfunction "2_2") (pintype "passive"))
      (node (ref "R1") (pin "2") (pinfunction "2_2") (pintype "passive"))
      (node (ref "SJ1") (pin "2") (pinfunction "2_2") (pintype "passive"))
    )
    (net (code "40") (name "AMPLI_OUT'") (class "Default")
      (node (ref "J4") (pin "2") (pinfunction "2_2") (pintype "passive"))
      (node (ref "J4") (pin "3") (pinfunction "3_3") (pintype "passive"))
      (node (ref "R1") (pin "1") (pinfunction "1_1") (pintype "passive"))
    )
    (net (code "41") (name "B0") (class "Default")
      (node (ref "U$1") (pin "P116") (pinfunction "IO_L64N_SCP4_0_P116") (pintype "bidirectional"))
      (node (ref "U3") (pin "55") (pinfunction "PD8_55") (pintype "bidirectional"))
    )
    (net (code "42") (name "B1") (class "Default")
      (node (ref "U$1") (pin "P117") (pinfunction "IO_L64P_SCP5_0_P117") (pintype "bidirectional"))
      (node (ref "U3") (pin "56") (pinfunction "PD9_56") (pintype "bidirectional"))
    )
    (net (code "43") (name "B2") (class "Default")
      (node (ref "U$1") (pin "P118") (pinfunction "IO_L63N_SCP6_0_P118") (pintype "bidirectional"))
      (node (ref "U3") (pin "57") (pinfunction "PD10_57") (pintype "bidirectional"))
    )
    (net (code "44") (name "B3") (class "Default")
      (node (ref "U$1") (pin "P119") (pinfunction "IO_L63P_SCP7_0_P119") (pintype "bidirectional"))
      (node (ref "U3") (pin "58") (pinfunction "PD11_58") (pintype "bidirectional"))
    )
    (net (code "45") (name "B4") (class "Default")
      (node (ref "U$1") (pin "P120") (pinfunction "IO_L62N_VREF_0_P120") (pintype "bidirectional"))
      (node (ref "U3") (pin "59") (pinfunction "PD12_59") (pintype "bidirectional"))
    )
    (net (code "46") (name "B5") (class "Default")
      (node (ref "U$1") (pin "P121") (pinfunction "IO_L62P_0_P121") (pintype "bidirectional"))
      (node (ref "U3") (pin "60") (pinfunction "PD13_60") (pintype "bidirectional"))
    )
    (net (code "47") (name "B6") (class "Default")
      (node (ref "U$1") (pin "P123") (pinfunction "IO_L37N_GCLK12_0_P123") (pintype "bidirectional"))
      (node (ref "U3") (pin "61") (pinfunction "PD14_61") (pintype "bidirectional"))
    )
    (net (code "48") (name "B7") (class "Default")
      (node (ref "U$1") (pin "P124") (pinfunction "IO_L37P_GCLK13_0_P124") (pintype "bidirectional"))
      (node (ref "U3") (pin "62") (pinfunction "PD15_62") (pintype "bidirectional"))
    )
    (net (code "49") (name "BOOT0") (class "Default")
      (node (ref "R24") (pin "1") (pinfunction "1_1") (pintype "passive"))
      (node (ref "R30") (pin "2") (pinfunction "2_2") (pintype "passive"))
      (node (ref "U3") (pin "94") (pinfunction "BOOT0_94") (pintype "bidirectional"))
    )
    (net (code "50") (name "BRIGHT") (class "Default")
      (node (ref "R33") (pin "1") (pinfunction "1_1") (pintype "passive"))
      (node (ref "R34") (pin "1") (pinfunction "1_1") (pintype "passive"))
      (node (ref "R35") (pin "1") (pinfunction "1_1") (pintype "passive"))
      (node (ref "U$1") (pin "P11") (pinfunction "IO_L49N_3_P11") (pintype "bidirectional"))
    )
    (net (code "51") (name "CC1") (class "Default")
      (node (ref "J3") (pin "A5") (pinfunction "CC1_A5") (pintype "bidirectional"))
    )
    (net (code "52") (name "CC2") (class "Default")
      (node (ref "J3") (pin "B5") (pinfunction "CC2_B5") (pintype "bidirectional"))
    )
    (net (code "53") (name "CFG_CLK") (class "Default")
      (node (ref "U$1") (pin "P17") (pinfunction "IO_L43P_GCLK23_3_P17") (pintype "bidirectional"))
      (node (ref "U3") (pin "35") (pinfunction "PB0_35") (pintype "bidirectional"))
    )
    (net (code "54") (name "CFG_DATA") (class "Default")
      (node (ref "U$1") (pin "P15") (pinfunction "IO_L44P_GCLK21_3_P15") (pintype "bidirectional"))
      (node (ref "U3") (pin "89") (pinfunction "PB3_89") (pintype "bidirectional"))
    )
    (net (code "55") (name "CFG_RESET") (class "Default")
      (node (ref "U$1") (pin "P16") (pinfunction "IO_L43N_GCLK22_IRDY2_3_P16") (pintype "bidirectional"))
      (node (ref "U3") (pin "36") (pinfunction "PB1_36") (pintype "bidirectional"))
    )
    (net (code "56") (name "COMPOSITE") (class "Default")
      (node (ref "J2") (pin "5") (pinfunction "5_5") (pintype "passive"))
      (node (ref "R4") (pin "1") (pinfunction "1_1") (pintype "passive"))
    )
    (net (code "57") (name "CSYNC") (class "Default")
      (node (ref "U$1") (pin "P10") (pinfunction "IO_L50P_3_P10") (pintype "bidirectional"))
      (node (ref "U1") (pin "16") (pinfunction "HSYNC_16") (pintype "input"))
    )
    (net (code "58") (name "CS_LLS") (class "Default")
      (node (ref "MICRO_SD1") (pin "2") (pinfunction "CD/DAT3_2") (pintype "bidirectional"))
      (node (ref "R21") (pin "2") (pinfunction "2_2") (pintype "passive"))
    )
    (net (code "59") (name "CTRL_CLK") (class "Default")
      (node (ref "U$1") (pin "P6") (pinfunction "IO_L52P_3_P6") (pintype "bidirectional"))
      (node (ref "U3") (pin "90") (pinfunction "PB4_90") (pintype "bidirectional"))
    )
    (net (code "60") (name "D0") (class "Default")
      (node (ref "4A") (pin "1") (pinfunction "P_1") (pintype "passive"))
      (node (ref "U$1") (pin "P23") (pinfunction "IO_L41N_GCLK26_3_P23") (pintype "bidirectional"))
      (node (ref "U2") (pin "13") (pinfunction "DQ0_13") (pintype "output"))
    )
    (net (code "61") (name "D1") (class "Default")
      (node (ref "5A") (pin "1") (pinfunction "P_1") (pintype "passive"))
      (node (ref "U$1") (pin "P26") (pinfunction "IO_L37N_3_P26") (pintype "bidirectional"))
      (node (ref "U2") (pin "14") (pinfunction "DQ1_14") (pintype "output"))
    )
    (net (code "62") (name "D2") (class "Default")
      (node (ref "6A") (pin "1") (pinfunction "P_1") (pintype "passive"))
      (node (ref "U$1") (pin "P27") (pinfunction "IO_L37P_3_P27") (pintype "bidirectional"))
      (node (ref "U2") (pin "15") (pinfunction "DQ2_15") (pintype "output"))
    )
    (net (code "63") (name "D3") (class "Default")
      (node (ref "9A") (pin "1") (pinfunction "P_1") (pintype "passive"))
      (node (ref "U$1") (pin "P34") (pinfunction "IO_L1N_VREF_3_P34") (pintype "bidirectional"))
      (node (ref "U2") (pin "17") (pinfunction "DQ3_17") (pintype "output"))
    )
    (net (code "64") (name "D4") (class "Default")
      (node (ref "10A") (pin "1") (pinfunction "P_1") (pintype "passive"))
      (node (ref "U$1") (pin "P39") (pinfunction "IO_L65P_INIT_B_2_P39") (pintype "bidirectional"))
      (node (ref "U2") (pin "18") (pinfunction "DQ4_18") (pintype "output"))
    )
    (net (code "65") (name "D5") (class "Default")
      (node (ref "8A") (pin "1") (pinfunction "P_1") (pintype "passive"))
      (node (ref "U$1") (pin "P32") (pinfunction "IO_L2N_3_P32") (pintype "bidirectional"))
      (node (ref "U2") (pin "19") (pinfunction "DQ5_19") (pintype "output"))
    )
    (net (code "66") (name "D6") (class "Default")
      (node (ref "7A") (pin "1") (pinfunction "P_1") (pintype "passive"))
      (node (ref "U$1") (pin "P29") (pinfunction "IO_L36N_3_P29") (pintype "bidirectional"))
      (node (ref "U2") (pin "20") (pinfunction "DQ6_20") (pintype "output"))
    )
    (net (code "67") (name "D7") (class "Default")
      (node (ref "1A") (pin "1") (pinfunction "P_1") (pintype "passive"))
      (node (ref "U$1") (pin "P21") (pinfunction "IO_L42N_GCLK24_3_P21") (pintype "bidirectional"))
      (node (ref "U2") (pin "21") (pinfunction "DQ7_21") (pintype "output"))
    )
    (net (code "68") (name "DI_LLS") (class "Default")
      (node (ref "MICRO_SD1") (pin "3") (pinfunction "CMD_3") (pintype "bidirectional"))
      (node (ref "R17") (pin "2") (pinfunction "2_2") (pintype "passive"))
    )
    (net (code "69") (name "DOWN") (class "Default")
      (node (ref "J2") (pin "2") (pinfunction "2_2") (pintype "passive"))
      (node (ref "U$1") (pin "P79") (pinfunction "IO_L47P_1_P79") (pintype "bidirectional"))
    )
    (net (code "70") (name "EN_M1_NOT") (class "Default")
      (node (ref "U$1") (pin "P140") (pinfunction "IO_L3P_0_P140") (pintype "bidirectional"))
      (node (ref "U3") (pin "25") (pinfunction "PA2_25") (pintype "bidirectional"))
    )
    (net (code "71") (name "FIRE") (class "Default")
      (node (ref "J2") (pin "6") (pinfunction "6_6") (pintype "passive"))
      (node (ref "U$1") (pin "P82") (pinfunction "IO_L45N_1_P82") (pintype "bidirectional"))
    )
    (net (code "72") (name "FLASH_CS") (class "Default")
      (node (ref "U$1") (pin "P38") (pinfunction "IO_L65N_CSO_B_2_P38") (pintype "bidirectional"))
      (node (ref "U4") (pin "1") (pinfunction "CS_1") (pintype "bidirectional"))
    )
    (net (code "73") (name "FLASH_MISO") (class "Default")
      (node (ref "U$1") (pin "P65") (pinfunction "IO_L3P_D0_DIN_MISO_MISO1_2_P65") (pintype "bidirectional"))
      (node (ref "U4") (pin "2") (pinfunction "MISO_2") (pintype "bidirectional"))
    )
    (net (code "74") (name "FLASH_MOSI") (class "Default")
      (node (ref "U$1") (pin "P64") (pinfunction "IO_L3N_MOSI_CSI_B_MISO0_2_P64") (pintype "bidirectional"))
      (node (ref "U4") (pin "5") (pinfunction "MOSI_5") (pintype "bidirectional"))
    )
    (net (code "75") (name "FLASH_SCLK") (class "Default")
      (node (ref "U$1") (pin "P70") (pinfunction "IO_L1P_CCLK_2_P70") (pintype "bidirectional"))
      (node (ref "U4") (pin "6") (pinfunction "SCK_6") (pintype "bidirectional"))
    )
    (net (code "76") (name "GET_CTRL_REG") (class "Default")
      (node (ref "U$1") (pin "P5") (pinfunction "IO_L52N_3_P5") (pintype "bidirectional"))
      (node (ref "U3") (pin "66") (pinfunction "PC9_66") (pintype "bidirectional"))
    )
    (net (code "77") (name "GET_DATA_REG") (class "Default")
      (node (ref "U$1") (pin "P2") (pinfunction "IO_L83P_3_P2") (pintype "bidirectional"))
      (node (ref "U3") (pin "78") (pinfunction "PC10_78") (pintype "bidirectional"))
    )
    (net (code "78") (name "GND") (class "Default")
      (node (ref "4B") (pin "1") (pinfunction "P_1") (pintype "passive"))
      (node (ref "5B") (pin "1") (pinfunction "P_1") (pintype "passive"))
      (node (ref "BT1") (pin "N") (pinfunction "NEG_N") (pintype "passive"))
      (node (ref "C10") (pin "2") (pinfunction "2_2") (pintype "passive"))
      (node (ref "C11") (pin "1") (pinfunction "1_1") (pintype "passive"))
      (node (ref "C12") (pin "1") (pinfunction "1_1") (pintype "passive"))
      (node (ref "C18") (pin "2") (pinfunction "2_2") (pintype "passive"))
      (node (ref "C19") (pin "2") (pinfunction "2_2") (pintype "passive"))
      (node (ref "C2") (pin "2") (pinfunction "2_2") (pintype "passive"))
      (node (ref "C22") (pin "1") (pinfunction "1_1") (pintype "passive"))
      (node (ref "C23") (pin "1") (pinfunction "1_1") (pintype "passive"))
      (node (ref "C24") (pin "2") (pinfunction "2_2") (pintype "passive"))
      (node (ref "C25") (pin "2") (pinfunction "2_2") (pintype "passive"))
      (node (ref "C26") (pin "2") (pinfunction "2_2") (pintype "passive"))
      (node (ref "C3") (pin "2") (pinfunction "2_2") (pintype "passive"))
      (node (ref "C33") (pin "2") (pinfunction "2_2") (pintype "passive"))
      (node (ref "C4") (pin "1") (pinfunction "1_1") (pintype "passive"))
      (node (ref "C5") (pin "1") (pinfunction "1_1") (pintype "passive"))
      (node (ref "C6") (pin "2") (pinfunction "2_2") (pintype "passive"))
      (node (ref "C7") (pin "2") (pinfunction "2_2") (pintype "passive"))
      (node (ref "C8") (pin "1") (pinfunction "1_1") (pintype "passive"))
      (node (ref "C9") (pin "1") (pinfunction "1_1") (pintype "passive"))
      (node (ref "IC2") (pin "1") (pinfunction "GND_1") (pintype "power_in"))
      (node (ref "IC5") (pin "1") (pinfunction "GND_1") (pintype "power_in"))
      (node (ref "J2") (pin "8") (pinfunction "8_8") (pintype "passive"))
      (node (ref "J3") (pin "A1_B12") (pinfunction "GND_A1_B12") (pintype "power_in"))
      (node (ref "J3") (pin "B1_A12") (pinfunction "GND_B1_A12") (pintype "power_in"))
      (node (ref "J3") (pin "SH1") (pinfunction "SHIELD_SH1") (pintype "passive"))
      (node (ref "J3") (pin "SH2") (pinfunction "SHIELD_SH2") (pintype "passive"))
      (node (ref "J3") (pin "SH3") (pinfunction "SHIELD_SH3") (pintype "passive"))
      (node (ref "J3") (pin "SH4") (pinfunction "SHIELD_SH4") (pintype "passive"))
      (node (ref "JP4") (pin "2") (pinfunction "2_2") (pintype "passive"))
      (node (ref "JP5") (pin "2") (pinfunction "2_2") (pintype "passive"))
      (node (ref "JP6") (pin "2") (pinfunction "2_2") (pintype "passive"))
      (node (ref "JP8") (pin "2") (pinfunction "2_2") (pintype "passive"))
      (node (ref "LED3") (pin "P1") (pinfunction "C_P1") (pintype "passive"))
      (node (ref "LED3") (pin "P2") (pinfunction "C_P2") (pintype "passive"))
      (node (ref "LED3") (pin "P3") (pinfunction "C_P3") (pintype "passive"))
      (node (ref "MICRO_SD1") (pin "6") (pinfunction "VSS_6") (pintype "power_in"))
      (node (ref "MICRO_SD1") (pin "MP1") (pinfunction "SHIELD_MP1") (pintype "power_in"))
      (node (ref "MICRO_SD1") (pin "MP2") (pinfunction "SHIELD_MP2") (pintype "power_in"))
      (node (ref "MICRO_SD1") (pin "MP3") (pinfunction "SHIELD_MP3") (pintype "power_in"))
      (node (ref "MICRO_SD1") (pin "MP4") (pinfunction "SHIELD_MP4") (pintype "power_in"))
      (node (ref "R19") (pin "2") (pinfunction "2_2") (pintype "passive"))
      (node (ref "R25") (pin "1") (pinfunction "1_1") (pintype "passive"))
      (node (ref "R27") (pin "2") (pinfunction "2_2") (pintype "passive"))
      (node (ref "R28") (pin "2") (pinfunction "2_2") (pintype "passive"))
      (node (ref "R30") (pin "1") (pinfunction "1_1") (pintype "passive"))
      (node (ref "S1") (pin "1") (pinfunction "P_1") (pintype "passive"))
      (node (ref "SJ2") (pin "1") (pinfunction "1_1") (pintype "passive"))
      (node (ref "U$1") (pin "P108") (pinfunction "GND_P108") (pintype "bidirectional"))
      (node (ref "U$1") (pin "P113") (pinfunction "GND_P113") (pintype "bidirectional"))
      (node (ref "U$1") (pin "P13") (pinfunction "GND_P13") (pintype "bidirectional"))
      (node (ref "U$1") (pin "P130") (pinfunction "GND_P130") (pintype "bidirectional"))
      (node (ref "U$1") (pin "P136") (pinfunction "GND_P136") (pintype "bidirectional"))
      (node (ref "U$1") (pin "P25") (pinfunction "GND_P25") (pintype "bidirectional"))
      (node (ref "U$1") (pin "P3") (pinfunction "GND_P3") (pintype "bidirectional"))
      (node (ref "U$1") (pin "P49") (pinfunction "GND_P49") (pintype "bidirectional"))
      (node (ref "U$1") (pin "P54") (pinfunction "GND_P54") (pintype "bidirectional"))
      (node (ref "U$1") (pin "P68") (pinfunction "GND_P68") (pintype "bidirectional"))
      (node (ref "U$1") (pin "P73") (pinfunction "SUSPEND_P73") (pintype "bidirectional"))
      (node (ref "U$1") (pin "P77") (pinfunction "GND_P77") (pintype "bidirectional"))
      (node (ref "U$1") (pin "P91") (pinfunction "GND_P91") (pintype "bidirectional"))
      (node (ref "U$1") (pin "P96") (pinfunction "GND_P96") (pintype "bidirectional"))
      (node (ref "U1") (pin "13") (pinfunction "DGND_13") (pintype "passive"))
      (node (ref "U1") (pin "2") (pinfunction "AGND_2") (pintype "passive"))
      (node (ref "U2") (pin "16") (pinfunction "VSS_16") (pintype "output"))
      (node (ref "U2") (pin "22") (pinfunction "CE_22") (pintype "input"))
      (node (ref "U3") (pin "10") (pinfunction "VSS_10") (pintype "bidirectional"))
      (node (ref "U3") (pin "20") (pinfunction "VSSA_20") (pintype "bidirectional"))
      (node (ref "U3") (pin "27") (pinfunction "VSS_27") (pintype "bidirectional"))
      (node (ref "U3") (pin "74") (pinfunction "VSS_74") (pintype "bidirectional"))
      (node (ref "U3") (pin "99") (pinfunction "VSS_99") (pintype "bidirectional"))
      (node (ref "U4") (pin "4") (pinfunction "GND_4") (pintype "power_in"))
      (node (ref "U5") (pin "7") (pinfunction "GND_7") (pintype "power_in"))
    )
    (net (code "79") (name "LEDB") (class "Default")
      (node (ref "R3") (pin "1") (pinfunction "1_1") (pintype "passive"))
      (node (ref "U3") (pin "64") (pinfunction "PC7_64") (pintype "bidirectional"))
    )
    (net (code "80") (name "LEDG") (class "Default")
      (node (ref "R13") (pin "1") (pinfunction "1_1") (pintype "passive"))
      (node (ref "U3") (pin "63") (pinfunction "PC6_63") (pintype "bidirectional"))
    )
    (net (code "81") (name "LEDR") (class "Default")
      (node (ref "R2") (pin "1") (pinfunction "1_1") (pintype "passive"))
      (node (ref "U3") (pin "65") (pinfunction "PC8_65") (pintype "bidirectional"))
    )
    (net (code "82") (name "LEFT") (class "Default")
      (node (ref "J2") (pin "3") (pinfunction "3_3") (pintype "passive"))
      (node (ref "U$1") (pin "P80") (pinfunction "IO_L46N_1_P80") (pintype "bidirectional"))
    )
    (net (code "83") (name "LE_IL") (class "Default")
      (node (ref "U$1") (pin "P14") (pinfunction "IO_L44N_GCLK20_3_P14") (pintype "bidirectional"))
      (node (ref "U3") (pin "7") (pinfunction "PC13_7") (pintype "bidirectional"))
    )
    (net (code "84") (name "MISO") (class "Default")
      (node (ref "R20") (pin "1") (pinfunction "1_1") (pintype "passive"))
      (node (ref "U3") (pin "31") (pinfunction "PA6_31") (pintype "bidirectional"))
    )
    (net (code "85") (name "MOSI") (class "Default")
      (node (ref "R17") (pin "1") (pinfunction "1_1") (pintype "passive"))
      (node (ref "U3") (pin "32") (pinfunction "PA7_32") (pintype "bidirectional"))
    )
    (net (code "86") (name "Net-(1B-P)") (class "Default")
      (node (ref "1B") (pin "1") (pinfunction "P_1") (pintype "passive"))
      (node (ref "D4") (pin "A") (pinfunction "A_A") (pintype "passive"))
    )
    (net (code "87") (name "Net-(BT1-POS)") (class "Default")
      (node (ref "BT1") (pin "P") (pinfunction "POS_P") (pintype "passive"))
      (node (ref "D3") (pin "2") (pinfunction "A2_2") (pintype "passive"))
      (node (ref "U3") (pin "16") (pinfunction "PC1_16") (pintype "bidirectional"))
    )
    (net (code "88") (name "Net-(C1-Pad2)") (class "Default")
      (node (ref "C1") (pin "2") (pinfunction "2_2") (pintype "passive"))
      (node (ref "R4") (pin "2") (pinfunction "2_2") (pintype "passive"))
    )
    (net (code "89") (name "Net-(C9-Pad2)") (class "Default")
      (node (ref "C9") (pin "2") (pinfunction "2_2") (pintype "passive"))
      (node (ref "R5") (pin "2") (pinfunction "2_2") (pintype "passive"))
    )
    (net (code "90") (name "Net-(C13-Pad2)") (class "Default")
      (node (ref "C13") (pin "2") (pinfunction "2_2") (pintype "passive"))
      (node (ref "R6") (pin "2") (pinfunction "2_2") (pintype "passive"))
    )
    (net (code "91") (name "Net-(D3-CC)") (class "Default")
      (node (ref "D3") (pin "3") (pinfunction "CC_3") (pintype "passive"))
      (node (ref "U3") (pin "6") (pinfunction "VBAT_6") (pintype "bidirectional"))
    )
    (net (code "92") (name "Net-(J3-DN1)") (class "Default")
      (node (ref "J3") (pin "A7") (pinfunction "DN1_A7") (pintype "bidirectional"))
      (node (ref "J3") (pin "B7") (pinfunction "DN2_B7") (pintype "bidirectional"))
      (node (ref "R26") (pin "1") (pinfunction "1_1") (pintype "passive"))
    )
    (net (code "93") (name "Net-(J3-DP1)") (class "Default")
      (node (ref "J3") (pin "A6") (pinfunction "DP1_A6") (pintype "bidirectional"))
      (node (ref "J3") (pin "B6") (pinfunction "DP2_B6") (pintype "bidirectional"))
      (node (ref "R22") (pin "1") (pinfunction "1_1") (pintype "passive"))
      (node (ref "R23") (pin "1") (pinfunction "1_1") (pintype "passive"))
    )
    (net (code "94") (name "Net-(J4-Pad4)") (class "Default")
      (node (ref "J4") (pin "4") (pinfunction "4_4") (pintype "passive"))
      (node (ref "JP1") (pin "2") (pinfunction "2_2") (pintype "passive"))
    )
    (net (code "95") (name "Net-(J4-Pad5)") (class "Default")
      (node (ref "J4") (pin "5") (pinfunction "5_5") (pintype "passive"))
      (node (ref "JP1") (pin "1") (pinfunction "1_1") (pintype "passive"))
    )
    (net (code "96") (name "Net-(JP7-Pad1)") (class "Default")
      (node (ref "JP7") (pin "1") (pinfunction "1_1") (pintype "passive"))
      (node (ref "R24") (pin "2") (pinfunction "2_2") (pintype "passive"))
    )
    (net (code "97") (name "Net-(JP7-Pad3)") (class "Default")
      (node (ref "JP7") (pin "3") (pinfunction "3_3") (pintype "passive"))
      (node (ref "R16") (pin "1") (pinfunction "1_1") (pintype "passive"))
    )
    (net (code "98") (name "Net-(LED2-PadA)") (class "Default")
      (node (ref "LED2") (pin "A") (pinfunction "A_A") (pintype "passive"))
      (node (ref "R11") (pin "2") (pinfunction "2_2") (pintype "passive"))
    )
    (net (code "99") (name "Net-(LED3A-A)") (class "Default")
      (node (ref "LED3") (pin "P6") (pinfunction "A_P6") (pintype "passive"))
      (node (ref "R3") (pin "2") (pinfunction "2_2") (pintype "passive"))
    )
    (net (code "100") (name "Net-(LED3B-A)") (class "Default")
      (node (ref "LED3") (pin "P5") (pinfunction "A_P5") (pintype "passive"))
      (node (ref "R13") (pin "2") (pinfunction "2_2") (pintype "passive"))
    )
    (net (code "101") (name "Net-(LED3C-A)") (class "Default")
      (node (ref "LED3") (pin "P4") (pinfunction "A_P4") (pintype "passive"))
      (node (ref "R2") (pin "2") (pinfunction "2_2") (pintype "passive"))
    )
    (net (code "102") (name "Net-(MICRO_SD1-DAT0)") (class "Default")
      (node (ref "MICRO_SD1") (pin "7") (pinfunction "DAT0_7") (pintype "bidirectional"))
      (node (ref "R20") (pin "2") (pinfunction "2_2") (pintype "passive"))
    )
    (net (code "103") (name "Net-(Q3-2)") (class "Default")
      (node (ref "C12") (pin "2") (pinfunction "2_2") (pintype "passive"))
      (node (ref "Q3") (pin "3") (pinfunction "2_3") (pintype "passive"))
      (node (ref "R14") (pin "2") (pinfunction "2_2") (pintype "passive"))
      (node (ref "U3") (pin "13") (pinfunction "PH1_13") (pintype "bidirectional"))
    )
    (net (code "104") (name "Net-(R10-Pad2)") (class "Default")
      (node (ref "R10") (pin "2") (pinfunction "2_2") (pintype "passive"))
      (node (ref "R32") (pin "2") (pinfunction "2_2") (pintype "passive"))
      (node (ref "R35") (pin "2") (pinfunction "2_2") (pintype "passive"))
    )
    (net (code "105") (name "Net-(R29-Pad2)") (class "Default")
      (node (ref "R29") (pin "2") (pinfunction "2_2") (pintype "passive"))
      (node (ref "R33") (pin "2") (pinfunction "2_2") (pintype "passive"))
      (node (ref "R8") (pin "2") (pinfunction "2_2") (pintype "passive"))
    )
    (net (code "106") (name "Net-(R31-Pad2)") (class "Default")
      (node (ref "R31") (pin "2") (pinfunction "2_2") (pintype "passive"))
      (node (ref "R34") (pin "2") (pinfunction "2_2") (pintype "passive"))
      (node (ref "R9") (pin "2") (pinfunction "2_2") (pintype "passive"))
    )
    (net (code "107") (name "Net-(U$1-PROGRAM_B_2)") (class "Default")
      (node (ref "R12") (pin "2") (pinfunction "2_2") (pintype "passive"))
      (node (ref "U$1") (pin "P37") (pinfunction "PROGRAM_B_2_P37") (pintype "bidirectional"))
    )
    (net (code "108") (name "Net-(U1-BIN)") (class "Default")
      (node (ref "R28") (pin "1") (pinfunction "1_1") (pintype "passive"))
      (node (ref "R8") (pin "1") (pinfunction "1_1") (pintype "passive"))
      (node (ref "U1") (pin "8") (pinfunction "BIN_8") (pintype "input"))
    )
    (net (code "109") (name "Net-(U1-COMP)") (class "Default")
      (node (ref "C1") (pin "1") (pinfunction "1_1") (pintype "passive"))
      (node (ref "U1") (pin "10") (pinfunction "COMP_10") (pintype "output"))
    )
    (net (code "110") (name "Net-(U1-GIN)") (class "Default")
      (node (ref "R27") (pin "1") (pinfunction "1_1") (pintype "passive"))
      (node (ref "R9") (pin "1") (pinfunction "1_1") (pintype "passive"))
      (node (ref "U1") (pin "7") (pinfunction "GIN_7") (pintype "input"))
    )
    (net (code "111") (name "Net-(U1-RIN)") (class "Default")
      (node (ref "R10") (pin "1") (pinfunction "1_1") (pintype "passive"))
      (node (ref "R19") (pin "1") (pinfunction "1_1") (pintype "passive"))
      (node (ref "U1") (pin "6") (pinfunction "RIN_6") (pintype "input"))
    )
    (net (code "112") (name "Net-(U3-PC14)") (class "Default")
      (node (ref "C22") (pin "2") (pinfunction "2_2") (pintype "passive"))
      (node (ref "Q4") (pin "2") (pinfunction "2_2") (pintype "passive"))
      (node (ref "U3") (pin "8") (pinfunction "PC14_8") (pintype "bidirectional"))
    )
    (net (code "113") (name "Net-(U3-PC15)") (class "Default")
      (node (ref "C23") (pin "2") (pinfunction "2_2") (pintype "passive"))
      (node (ref "Q4") (pin "1") (pinfunction "1_1") (pintype "passive"))
      (node (ref "U3") (pin "9") (pinfunction "PC15_9") (pintype "bidirectional"))
    )
    (net (code "114") (name "Net-(U3-PH0)") (class "Default")
      (node (ref "C11") (pin "2") (pinfunction "2_2") (pintype "passive"))
      (node (ref "Q3") (pin "1") (pinfunction "1_1") (pintype "passive"))
      (node (ref "R14") (pin "1") (pinfunction "1_1") (pintype "passive"))
      (node (ref "U3") (pin "12") (pinfunction "PH0_12") (pintype "bidirectional"))
    )
    (net (code "115") (name "Net-(U3-VCAP_1)") (class "Default")
      (node (ref "C10") (pin "1") (pinfunction "1_1") (pintype "passive"))
      (node (ref "U3") (pin "49") (pinfunction "VCAP_1_49") (pintype "bidirectional"))
    )
    (net (code "116") (name "Net-(U3-VCAP_2)") (class "Default")
      (node (ref "C7") (pin "1") (pinfunction "1_1") (pintype "passive"))
      (node (ref "U3") (pin "73") (pinfunction "VCAP_2_73") (pintype "bidirectional"))
    )
    (net (code "117") (name "Net-(U5-IN+)") (class "Default")
      (node (ref "R6") (pin "1") (pinfunction "1_1") (pintype "passive"))
      (node (ref "U5") (pin "3") (pinfunction "IN+_3") (pintype "input"))
    )
    (net (code "118") (name "Net-(U5-IN-)") (class "Default")
      (node (ref "R5") (pin "1") (pinfunction "1_1") (pintype "passive"))
      (node (ref "U5") (pin "4") (pinfunction "IN-_4") (pintype "input"))
    )
    (net (code "119") (name "Net-(U5-VO+)") (class "Default")
      (node (ref "C14") (pin "1") (pinfunction "1_1") (pintype "passive"))
      (node (ref "U5") (pin "5") (pinfunction "VO+_5") (pintype "output"))
    )
    (net (code "120") (name "Net-(U5-VO-)") (class "Default")
      (node (ref "J4") (pin "1") (pinfunction "1_1") (pintype "passive"))
      (node (ref "SJ2") (pin "2") (pinfunction "2_2") (pintype "passive"))
      (node (ref "U5") (pin "8") (pinfunction "VO-_8") (pintype "output"))
    )
    (net (code "121") (name "Net-(U5-~{SD})") (class "Default")
      (node (ref "R7") (pin "1") (pinfunction "1_1") (pintype "passive"))
      (node (ref "U5") (pin "1") (pinfunction "~{SD}_1") (pintype "input"))
    )
    (net (code "122") (name "O0") (class "Default")
      (node (ref "U$1") (pin "P126") (pinfunction "IO_L36N_GCLK14_0_P126") (pintype "bidirectional"))
      (node (ref "U3") (pin "81") (pinfunction "PD0_81") (pintype "bidirectional"))
    )
    (net (code "123") (name "O1") (class "Default")
      (node (ref "U$1") (pin "P127") (pinfunction "IO_L36P_GCLK15_0_P127") (pintype "bidirectional"))
      (node (ref "U3") (pin "82") (pinfunction "PD1_82") (pintype "bidirectional"))
    )
    (net (code "124") (name "O2") (class "Default")
      (node (ref "U$1") (pin "P131") (pinfunction "IO_L35N_GCLK16_0_P131") (pintype "bidirectional"))
      (node (ref "U3") (pin "83") (pinfunction "PD2_83") (pintype "bidirectional"))
    )
    (net (code "125") (name "O3") (class "Default")
      (node (ref "U$1") (pin "P132") (pinfunction "IO_L35P_GCLK17_0_P132") (pintype "bidirectional"))
      (node (ref "U3") (pin "84") (pinfunction "PD3_84") (pintype "bidirectional"))
    )
    (net (code "126") (name "O4") (class "Default")
      (node (ref "U$1") (pin "P133") (pinfunction "IO_L34N_GCLK18_0_P133") (pintype "bidirectional"))
      (node (ref "U3") (pin "85") (pinfunction "PD4_85") (pintype "bidirectional"))
    )
    (net (code "127") (name "O5") (class "Default")
      (node (ref "U$1") (pin "P134") (pinfunction "IO_L34P_GCLK19_0_P134") (pintype "bidirectional"))
      (node (ref "U3") (pin "86") (pinfunction "PD5_86") (pintype "bidirectional"))
    )
    (net (code "128") (name "O6") (class "Default")
      (node (ref "U$1") (pin "P137") (pinfunction "IO_L4N_0_P137") (pintype "bidirectional"))
      (node (ref "U3") (pin "87") (pinfunction "PD6_87") (pintype "bidirectional"))
    )
    (net (code "129") (name "O7") (class "Default")
      (node (ref "U$1") (pin "P138") (pinfunction "IO_L4P_0_P138") (pintype "bidirectional"))
      (node (ref "U3") (pin "88") (pinfunction "PD7_88") (pintype "bidirectional"))
    )
    (net (code "130") (name "PA11{slash}USB_DN") (class "Default")
      (node (ref "R26") (pin "2") (pinfunction "2_2") (pintype "passive"))
      (node (ref "U3") (pin "70") (pinfunction "PA11_70") (pintype "bidirectional"))
    )
    (net (code "131") (name "PA12{slash}USB_DP") (class "Default")
      (node (ref "R23") (pin "2") (pinfunction "2_2") (pintype "passive"))
      (node (ref "U3") (pin "71") (pinfunction "PA12_71") (pintype "bidirectional"))
    )
    (net (code "132") (name "PA13{slash}JTMS{slash}SWDIO") (class "Default")
      (node (ref "JP8") (pin "1") (pinfunction "1_1") (pintype "passive"))
      (node (ref "U3") (pin "72") (pinfunction "PA13_72") (pintype "bidirectional"))
    )
    (net (code "133") (name "PA14{slash}JTCK{slash}SWCLK") (class "Default")
      (node (ref "JP8") (pin "3") (pinfunction "3_3") (pintype "passive"))
      (node (ref "U3") (pin "76") (pinfunction "PA14_76") (pintype "bidirectional"))
    )
    (net (code "134") (name "PAGE_A8") (class "Default")
      (node (ref "U$1") (pin "P143") (pinfunction "IO_L1N_VREF_0_P143") (pintype "bidirectional"))
      (node (ref "U3") (pin "24") (pinfunction "PA1_24") (pintype "bidirectional"))
    )
    (net (code "135") (name "PAL-NTSC") (class "Default")
      (node (ref "U$1") (pin "P22") (pinfunction "IO_L42P_GCLK25_TRDY2_3_P22") (pintype "bidirectional"))
      (node (ref "U1") (pin "1") (pinfunction "STND_1") (pintype "input"))
    )
    (net (code "136") (name "PB2{slash}BOOT1") (class "Default")
      (node (ref "R16") (pin "2") (pinfunction "2_2") (pintype "passive"))
      (node (ref "R25") (pin "2") (pinfunction "2_2") (pintype "passive"))
      (node (ref "U3") (pin "37") (pinfunction "PB2_37") (pintype "bidirectional"))
    )
    (net (code "137") (name "PS2_CLOCK") (class "Default")
      (node (ref "JP6") (pin "3") (pinfunction "3_3") (pintype "passive"))
      (node (ref "U3") (pin "80") (pinfunction "PC12_80") (pintype "bidirectional"))
    )
    (net (code "138") (name "PS2_DATA") (class "Default")
      (node (ref "JP6") (pin "4") (pinfunction "4_4") (pintype "passive"))
      (node (ref "U3") (pin "79") (pinfunction "PC11_79") (pintype "bidirectional"))
    )
    (net (code "139") (name "RESET") (class "Default")
      (node (ref "C5") (pin "2") (pinfunction "2_2") (pintype "passive"))
      (node (ref "D1") (pin "A") (pinfunction "A_A") (pintype "passive"))
      (node (ref "R15") (pin "1") (pinfunction "1_1") (pintype "passive"))
      (node (ref "S1") (pin "2") (pinfunction "S_2") (pintype "passive"))
      (node (ref "U3") (pin "14") (pinfunction "NRST_14") (pintype "bidirectional"))
    )
    (net (code "140") (name "RIGHT") (class "Default")
      (node (ref "J2") (pin "4") (pinfunction "4_4") (pintype "passive"))
      (node (ref "U$1") (pin "P81") (pinfunction "IO_L46P_1_P81") (pintype "bidirectional"))
    )
    (net (code "141") (name "ROM_WR_EN") (class "Default")
      (node (ref "U$1") (pin "P142") (pinfunction "IO_L2P_0_P142") (pintype "bidirectional"))
      (node (ref "U3") (pin "67") (pinfunction "PA8_67") (pintype "bidirectional"))
    )
    (net (code "142") (name "RST_CTRL_REG") (class "Default")
      (node (ref "U$1") (pin "P1") (pinfunction "IO_L83N_VREF_3_P1") (pintype "bidirectional"))
      (node (ref "U3") (pin "53") (pinfunction "PB14_53") (pintype "bidirectional"))
    )
    (net (code "143") (name "RST_DATA_REG") (class "Default")
      (node (ref "U$1") (pin "P144") (pinfunction "IO_L1P_HSWAPEN_0_P144") (pintype "bidirectional"))
      (node (ref "U3") (pin "91") (pinfunction "PB5_91") (pintype "bidirectional"))
    )
    (net (code "144") (name "SCK_LLS") (class "Default")
      (node (ref "MICRO_SD1") (pin "5") (pinfunction "CLK_5") (pintype "bidirectional"))
      (node (ref "R18") (pin "2") (pinfunction "2_2") (pintype "passive"))
    )
    (net (code "145") (name "SCL") (class "Default")
      (node (ref "U3") (pin "92") (pinfunction "PB6_92") (pintype "bidirectional"))
    )
    (net (code "146") (name "SCLK") (class "Default")
      (node (ref "R18") (pin "1") (pinfunction "1_1") (pintype "passive"))
      (node (ref "U3") (pin "30") (pinfunction "PA5_30") (pintype "bidirectional"))
    )
    (net (code "147") (name "SDA") (class "Default")
      (node (ref "U3") (pin "93") (pinfunction "PB7_93") (pintype "bidirectional"))
    )
    (net (code "148") (name "SD_LED") (class "Default")
      (node (ref "LED2") (pin "C") (pinfunction "C_C") (pintype "passive"))
      (node (ref "U3") (pin "15") (pinfunction "PC0_15") (pintype "bidirectional"))
    )
    (net (code "149") (name "SEL_128CHARS") (class "Default")
      (node (ref "U$1") (pin "P141") (pinfunction "IO_L2N_0_P141") (pintype "bidirectional"))
      (node (ref "U3") (pin "77") (pinfunction "PA15_77") (pintype "bidirectional"))
    )
    (net (code "150") (name "SOUND") (class "Default")
      (node (ref "C13") (pin "1") (pinfunction "1_1") (pintype "passive"))
      (node (ref "SJ1") (pin "1") (pinfunction "1_1") (pintype "passive"))
      (node (ref "U3") (pin "29") (pinfunction "PA4_29") (pintype "bidirectional"))
    )
    (net (code "151") (name "SPARE") (class "Default")
      (node (ref "U$1") (pin "P75") (pinfunction "IO_L74P_AWAKE_1_P75") (pintype "bidirectional"))
    )
    (net (code "152") (name "SS_SD") (class "Default")
      (node (ref "R21") (pin "1") (pinfunction "1_1") (pintype "passive"))
      (node (ref "U3") (pin "54") (pinfunction "PB15_54") (pintype "bidirectional"))
    )
    (net (code "153") (name "TCK") (class "Default")
      (node (ref "JP3") (pin "1") (pinfunction "1_1") (pintype "passive"))
      (node (ref "U$1") (pin "P109") (pinfunction "TCK_P109") (pintype "bidirectional"))
    )
    (net (code "154") (name "TDI") (class "Default")
      (node (ref "JP3") (pin "3") (pinfunction "3_3") (pintype "passive"))
      (node (ref "U$1") (pin "P110") (pinfunction "TDI_P110") (pintype "bidirectional"))
    )
    (net (code "155") (name "TDO") (class "Default")
      (node (ref "JP3") (pin "2") (pinfunction "2_2") (pintype "passive"))
      (node (ref "U$1") (pin "P106") (pinfunction "TDO_P106") (pintype "bidirectional"))
    )
    (net (code "156") (name "TMS") (class "Default")
      (node (ref "JP3") (pin "4") (pinfunction "4_4") (pintype "passive"))
      (node (ref "U$1") (pin "P107") (pinfunction "TMS_P107") (pintype "bidirectional"))
    )
    (net (code "157") (name "UART_RX") (class "Default")
      (node (ref "JP4") (pin "3") (pinfunction "3_3") (pintype "passive"))
      (node (ref "U3") (pin "69") (pinfunction "PA10_69") (pintype "bidirectional"))
    )
    (net (code "158") (name "UART_TX") (class "Default")
      (node (ref "JP4") (pin "4") (pinfunction "4_4") (pintype "passive"))
      (node (ref "U3") (pin "68") (pinfunction "PA9_68") (pintype "bidirectional"))
    )
    (net (code "159") (name "UP") (class "Default")
      (node (ref "J2") (pin "1") (pinfunction "1_1") (pintype "passive"))
      (node (ref "U$1") (pin "P78") (pinfunction "IO_L47N_1_P78") (pintype "bidirectional"))
    )
    (net (code "160") (name "VCC") (class "Default")
      (node (ref "23B") (pin "1") (pinfunction "P_1") (pintype "passive"))
      (node (ref "2A") (pin "1") (pinfunction "P_1") (pintype "passive"))
      (node (ref "C3") (pin "1") (pinfunction "1_1") (pintype "passive"))
      (node (ref "C8") (pin "2") (pinfunction "2_2") (pintype "passive"))
      (node (ref "D1") (pin "C") (pinfunction "C_C") (pintype "passive"))
      (node (ref "D2") (pin "C") (pinfunction "C_C") (pintype "passive"))
      (node (ref "D4") (pin "C") (pinfunction "C_C") (pintype "passive"))
      (node (ref "IC2") (pin "3") (pinfunction "VIN_3") (pintype "input"))
      (node (ref "IC5") (pin "3") (pinfunction "VIN_3") (pintype "input"))
      (node (ref "JP4") (pin "1") (pinfunction "1_1") (pintype "passive"))
      (node (ref "JP6") (pin "1") (pinfunction "1_1") (pintype "passive"))
      (node (ref "R11") (pin "1") (pinfunction "1_1") (pintype "passive"))
      (node (ref "R15") (pin "2") (pinfunction "2_2") (pintype "passive"))
      (node (ref "R22") (pin "2") (pinfunction "2_2") (pintype "passive"))
      (node (ref "R7") (pin "2") (pinfunction "2_2") (pintype "passive"))
      (node (ref "U1") (pin "12") (pinfunction "SELECT_12") (pintype "input"))
      (node (ref "U1") (pin "14") (pinfunction "DPOS_14") (pintype "power_in"))
      (node (ref "U1") (pin "15") (pinfunction "VSYNC_15") (pintype "input"))
      (node (ref "U1") (pin "4") (pinfunction "APOS_4") (pintype "power_in"))
      (node (ref "U1") (pin "5") (pinfunction "ENCD_5") (pintype "input"))
      (node (ref "U2") (pin "32") (pinfunction "VCC_32") (pintype "power_in"))
      (node (ref "U5") (pin "6") (pinfunction "VDD_6") (pintype "power_in"))
    )
    (net (code "161") (name "VCC_USB") (class "Default")
      (node (ref "D2") (pin "A") (pinfunction "A_A") (pintype "passive"))
      (node (ref "J3") (pin "A4_B9") (pinfunction "VBUS_A4_B9") (pintype "power_in"))
      (node (ref "J3") (pin "B4_A9") (pinfunction "VBUS_B4_A9") (pintype "power_in"))
    )
    (net (code "162") (name "VID_CLK") (class "Default")
      (node (ref "U$1") (pin "P56") (pinfunction "IO_L30P_GCLK1_D13_2_P56") (pintype "bidirectional"))
      (node (ref "U1") (pin "3") (pinfunction "FIN_3") (pintype "input"))
    )
    (net (code "163") (name "V_BLUE") (class "Default")
      (node (ref "R29") (pin "1") (pinfunction "1_1") (pintype "passive"))
      (node (ref "U$1") (pin "P9") (pinfunction "IO_L50N_3_P9") (pintype "bidirectional"))
    )
    (net (code "164") (name "V_GREEN") (class "Default")
      (node (ref "R31") (pin "1") (pinfunction "1_1") (pintype "passive"))
      (node (ref "U$1") (pin "P8") (pinfunction "IO_L51P_3_P8") (pintype "bidirectional"))
    )
    (net (code "165") (name "V_RED") (class "Default")
      (node (ref "R32") (pin "1") (pinfunction "1_1") (pintype "passive"))
      (node (ref "U$1") (pin "P7") (pinfunction "IO_L51N_3_P7") (pintype "bidirectional"))
    )
    (net (code "166") (name "unconnected-(J2-Pad7)") (class "Default")
      (node (ref "J2") (pin "7") (pinfunction "7_7") (pintype "passive"))
    )
    (net (code "167") (name "unconnected-(J2-Pad9)") (class "Default")
      (node (ref "J2") (pin "9") (pinfunction "9_9") (pintype "passive"))
    )
    (net (code "168") (name "unconnected-(MICRO_SD1-CD-PadCD1)") (class "Default")
      (node (ref "MICRO_SD1") (pin "CD1") (pinfunction "CD_CD1") (pintype "passive"))
    )
    (net (code "169") (name "unconnected-(MICRO_SD1-DAT1-Pad8)") (class "Default")
      (node (ref "MICRO_SD1") (pin "8") (pinfunction "DAT1_8") (pintype "bidirectional"))
    )
    (net (code "170") (name "unconnected-(MICRO_SD1-DAT2-Pad1)") (class "Default")
      (node (ref "MICRO_SD1") (pin "1") (pinfunction "DAT2_1") (pintype "bidirectional"))
    )
    (net (code "171") (name "unconnected-(U$1-CMPCS_B_2-PadP72)") (class "Default")
      (node (ref "U$1") (pin "P72") (pinfunction "CMPCS_B_2_P72") (pintype "bidirectional"))
    )
    (net (code "172") (name "unconnected-(U$1-DONE_2-PadP71)") (class "Default")
      (node (ref "U$1") (pin "P71") (pinfunction "DONE_2_P71") (pintype "bidirectional"))
    )
    (net (code "173") (name "unconnected-(U1-CRMA-Pad9)") (class "Default")
      (node (ref "U1") (pin "9") (pinfunction "CRMA_9") (pintype "output"))
    )
    (net (code "174") (name "unconnected-(U1-LUMA-Pad11)") (class "Default")
      (node (ref "U1") (pin "11") (pinfunction "LUMA_11") (pintype "output"))
    )
    (net (code "175") (name "unconnected-(U3-PB8-Pad95)") (class "Default")
      (node (ref "U3") (pin "95") (pinfunction "PB8_95") (pintype "bidirectional"))
    )
    (net (code "176") (name "unconnected-(U3-PC2-Pad17)") (class "Default")
      (node (ref "U3") (pin "17") (pinfunction "PC2_17") (pintype "bidirectional"))
    )
    (net (code "177") (name "unconnected-(U3-PC3-Pad18)") (class "Default")
      (node (ref "U3") (pin "18") (pinfunction "PC3_18") (pintype "bidirectional"))
    )
    (net (code "178") (name "unconnected-(U3-PC4-Pad33)") (class "Default")
      (node (ref "U3") (pin "33") (pinfunction "PC4_33") (pintype "bidirectional"))
    )
    (net (code "179") (name "unconnected-(U3-PC5-Pad34)") (class "Default")
      (node (ref "U3") (pin "34") (pinfunction "PC5_34") (pintype "bidirectional"))
    )
    (net (code "180") (name "unconnected-(U5-NC-Pad2)") (class "Default")
      (node (ref "U5") (pin "2") (pinfunction "NC_2") (pintype "no_connect"))
    )
    (net (code "181") (name "{slash}BUSAK") (class "Default")
      (node (ref "18A") (pin "1") (pinfunction "P_1") (pintype "passive"))
    )
    (net (code "182") (name "{slash}BUSRQ") (class "Default")
      (node (ref "20A") (pin "1") (pinfunction "P_1") (pintype "passive"))
    )
    (net (code "183") (name "{slash}CLOCK") (class "Default")
      (node (ref "6B") (pin "1") (pinfunction "P_1") (pintype "passive"))
      (node (ref "U$1") (pin "P24") (pinfunction "IO_L41P_GCLK27_3_P24") (pintype "bidirectional"))
    )
    (net (code "184") (name "{slash}HALT") (class "Default")
      (node (ref "13A") (pin "1") (pinfunction "P_1") (pintype "passive"))
      (node (ref "U$1") (pin "P46") (pinfunction "IO_L49P_D3_2_P46") (pintype "bidirectional"))
    )
    (net (code "185") (name "{slash}IORQ") (class "Default")
      (node (ref "15A") (pin "1") (pinfunction "P_1") (pintype "passive"))
      (node (ref "U$1") (pin "P51") (pinfunction "IO_L31P_GCLK31_D14_2_P51") (pintype "bidirectional"))
    )
    (net (code "186") (name "{slash}M1") (class "Default")
      (node (ref "22A") (pin "1") (pinfunction "P_1") (pintype "passive"))
      (node (ref "U$1") (pin "P67") (pinfunction "IO_L2P_CMPCLK_2_P67") (pintype "bidirectional"))
    )
    (net (code "187") (name "{slash}MEM_OE") (class "Default")
      (node (ref "U$1") (pin "P92") (pinfunction "IO_L41N_GCLK8_1_P92") (pintype "bidirectional"))
      (node (ref "U2") (pin "24") (pinfunction "OE_24") (pintype "input"))
    )
    (net (code "188") (name "{slash}MREQ") (class "Default")
      (node (ref "14A") (pin "1") (pinfunction "P_1") (pintype "passive"))
      (node (ref "U$1") (pin "P48") (pinfunction "IO_L48P_D7_2_P48") (pintype "bidirectional"))
    )
    (net (code "189") (name "{slash}NMI") (class "Default")
      (node (ref "12A") (pin "1") (pinfunction "P_1") (pintype "passive"))
      (node (ref "U$1") (pin "P44") (pinfunction "IO_L62P_D5_2_P44") (pintype "bidirectional"))
    )
    (net (code "190") (name "{slash}OE_OL") (class "Default")
      (node (ref "U$1") (pin "P12") (pinfunction "IO_L49P_3_P12") (pintype "bidirectional"))
      (node (ref "U3") (pin "47") (pinfunction "PB10_47") (pintype "bidirectional"))
    )
    (net (code "191") (name "{slash}RD") (class "Default")
      (node (ref "16A") (pin "1") (pinfunction "P_1") (pintype "passive"))
      (node (ref "U$1") (pin "P105") (pinfunction "IO_L1P_1_P105") (pintype "bidirectional"))
    )
    (net (code "192") (name "{slash}RESET") (class "Default")
      (node (ref "21A") (pin "1") (pinfunction "P_1") (pintype "passive"))
      (node (ref "U$1") (pin "P139") (pinfunction "IO_L3N_0_P139") (pintype "bidirectional"))
      (node (ref "U3") (pin "96") (pinfunction "PB9_96") (pintype "bidirectional"))
    )
    (net (code "193") (name "{slash}RFSH") (class "Default")
      (node (ref "23A") (pin "1") (pinfunction "P_1") (pintype "passive"))
      (node (ref "U$1") (pin "P74") (pinfunction "IO_L74N_DOUT_BUSY_1_P74") (pintype "bidirectional"))
    )
    (net (code "194") (name "{slash}WAIT") (class "Default")
      (node (ref "19A") (pin "1") (pinfunction "P_1") (pintype "passive"))
      (node (ref "U3") (pin "23") (pinfunction "PA0_23") (pintype "bidirectional"))
    )
    (net (code "195") (name "{slash}WR") (class "Default")
      (node (ref "17A") (pin "1") (pinfunction "P_1") (pintype "passive"))
      (node (ref "U$1") (pin "P58") (pinfunction "IO_L14P_D11_2_P58") (pintype "bidirectional"))
    )
    (net (code "196") (name "{slash}WR'") (class "Default")
      (node (ref "U$1") (pin "P102") (pinfunction "IO_L32P_1_P102") (pintype "bidirectional"))
      (node (ref "U2") (pin "29") (pinfunction "WE_29") (pintype "input"))
      (node (ref "U3") (pin "26") (pinfunction "PA3_26") (pintype "bidirectional"))
    )
  )
)
